# M868Hvrs1.net
KiCad netlist of a schematic drawn in EAGLE
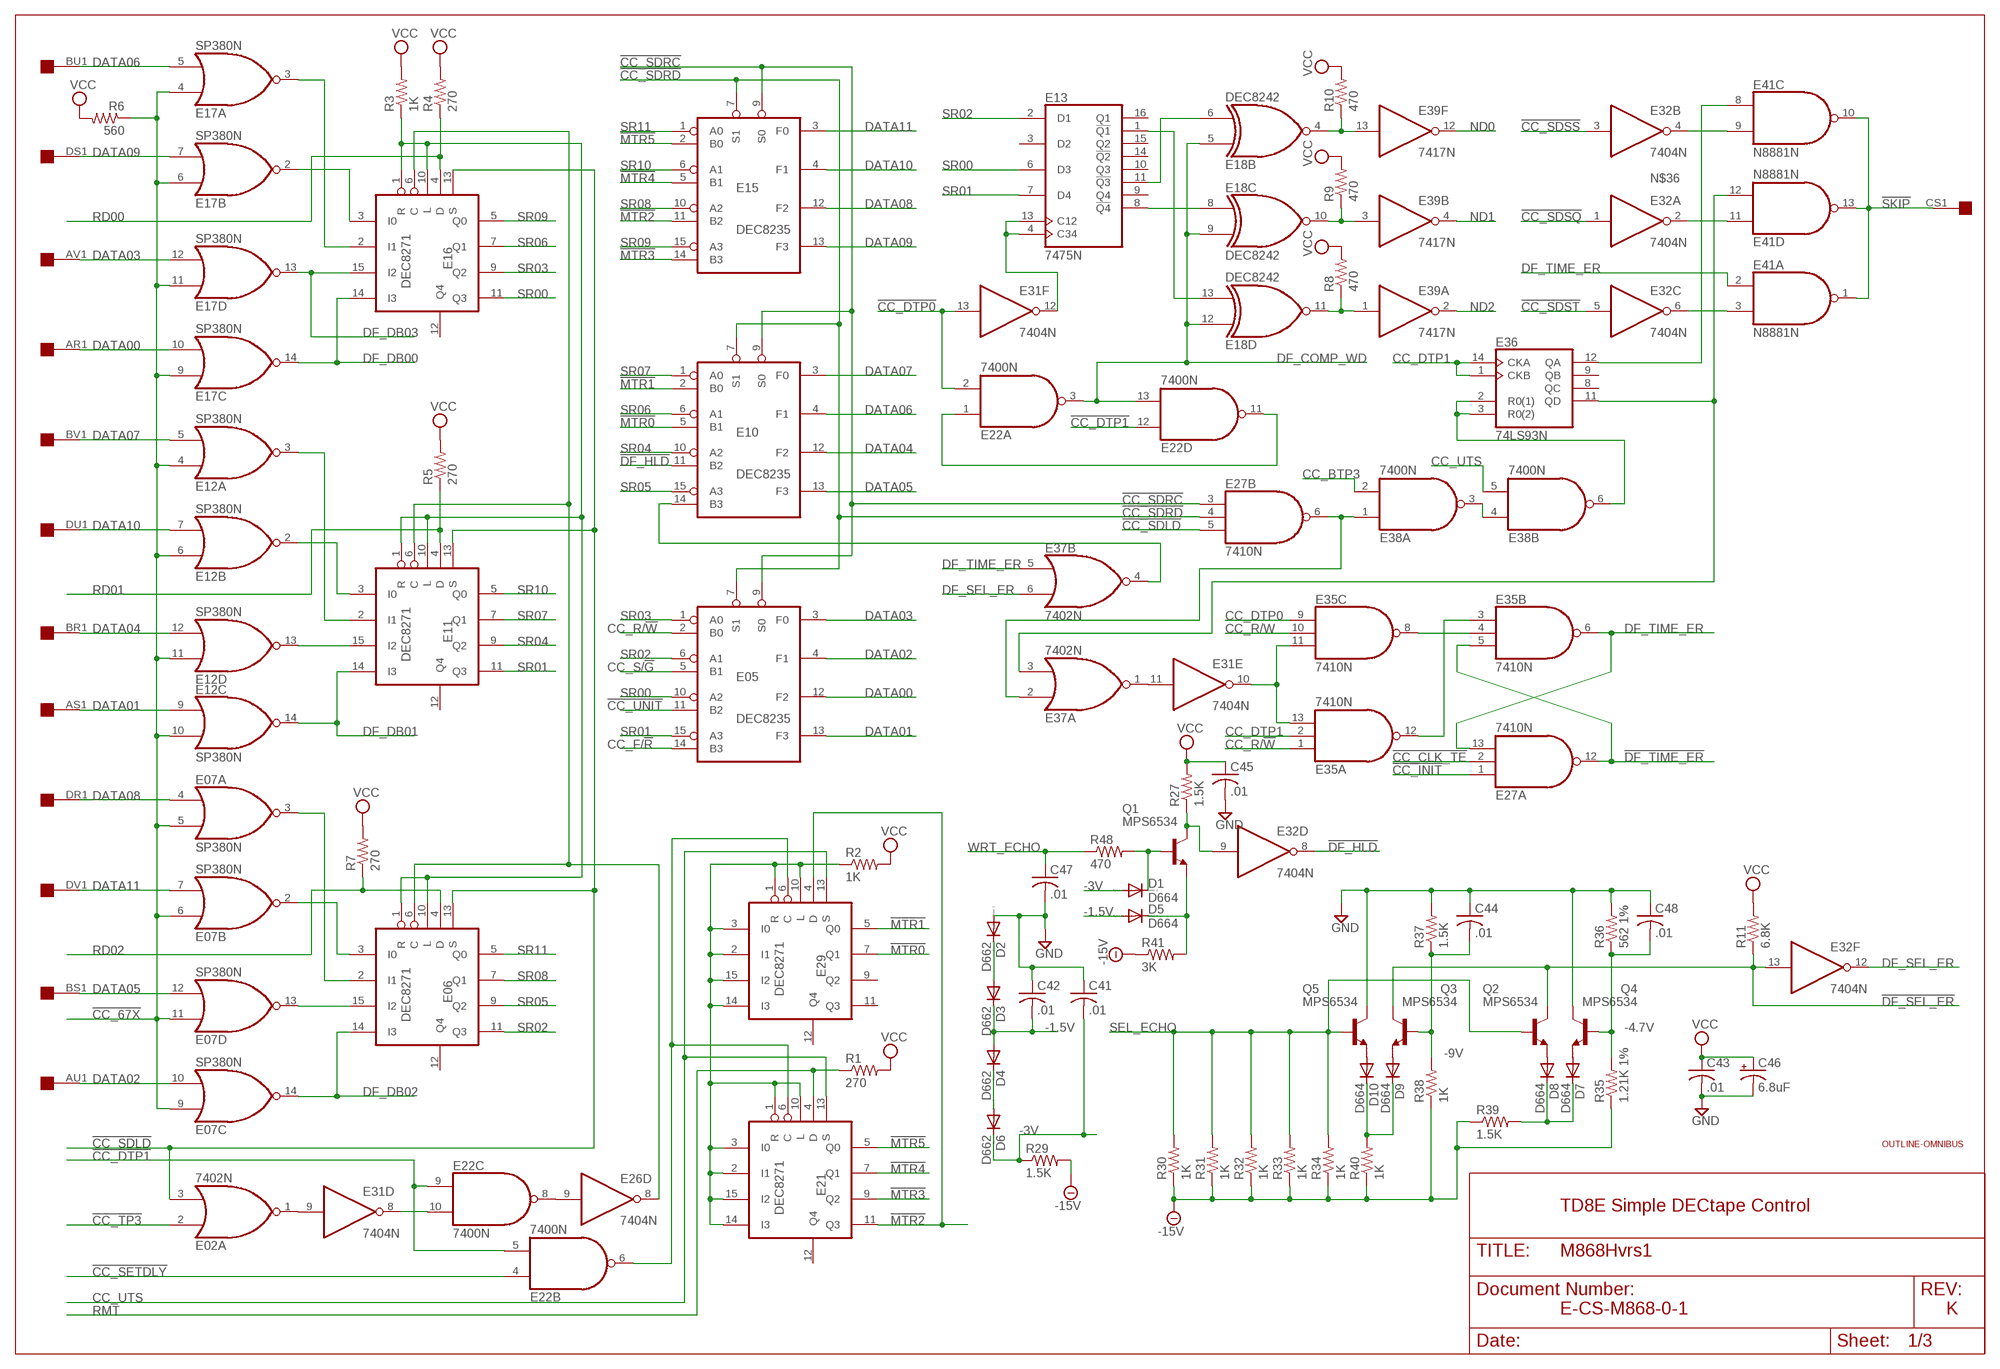
[diagram p0: schematic, sheet 1]
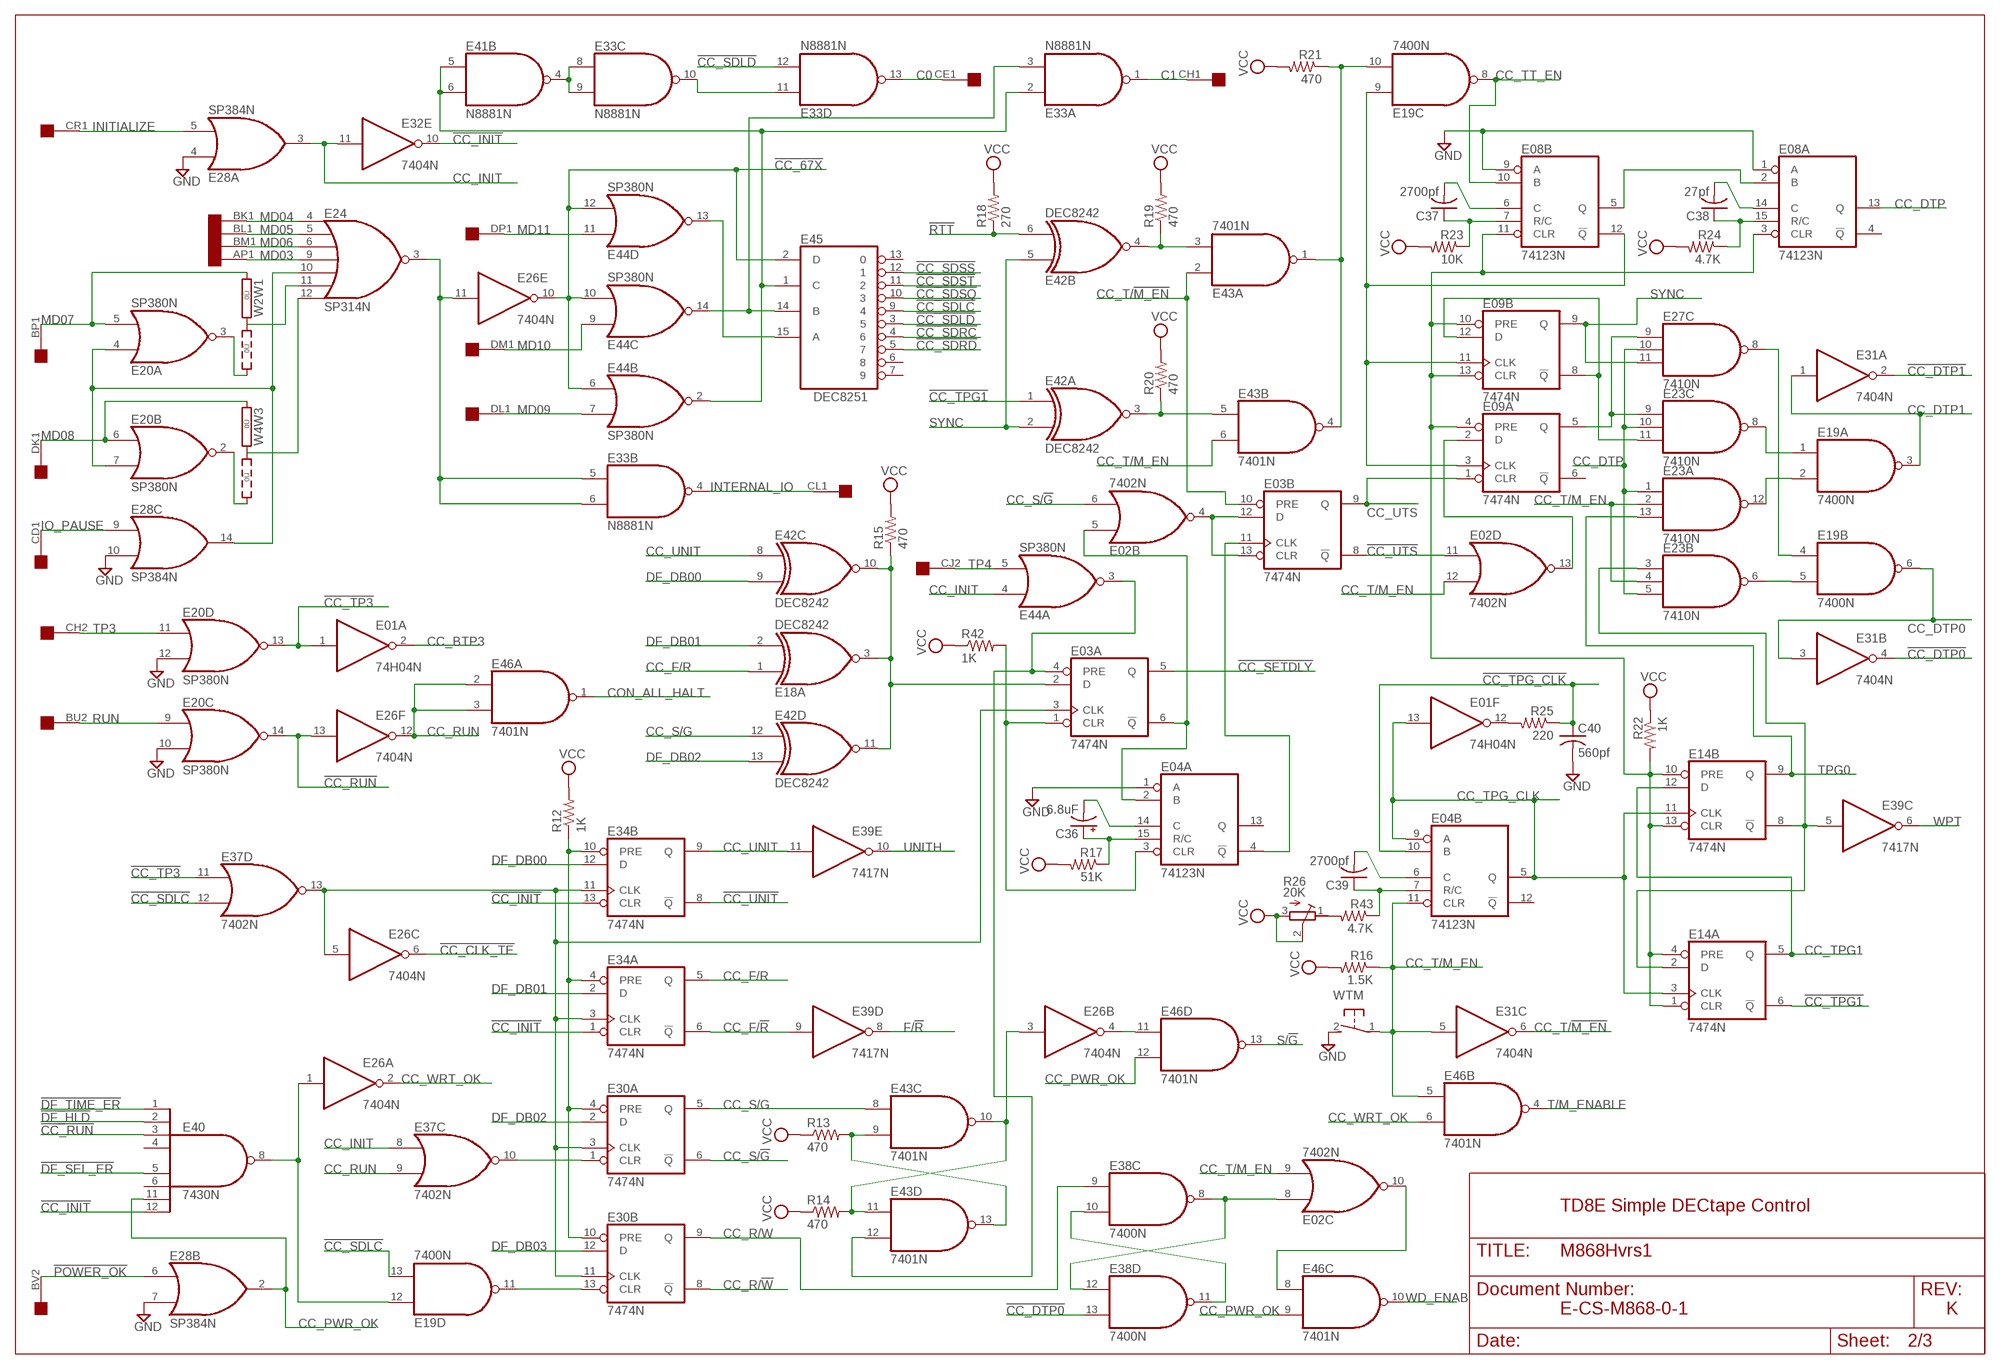
[diagram p1: schematic, sheet 2]
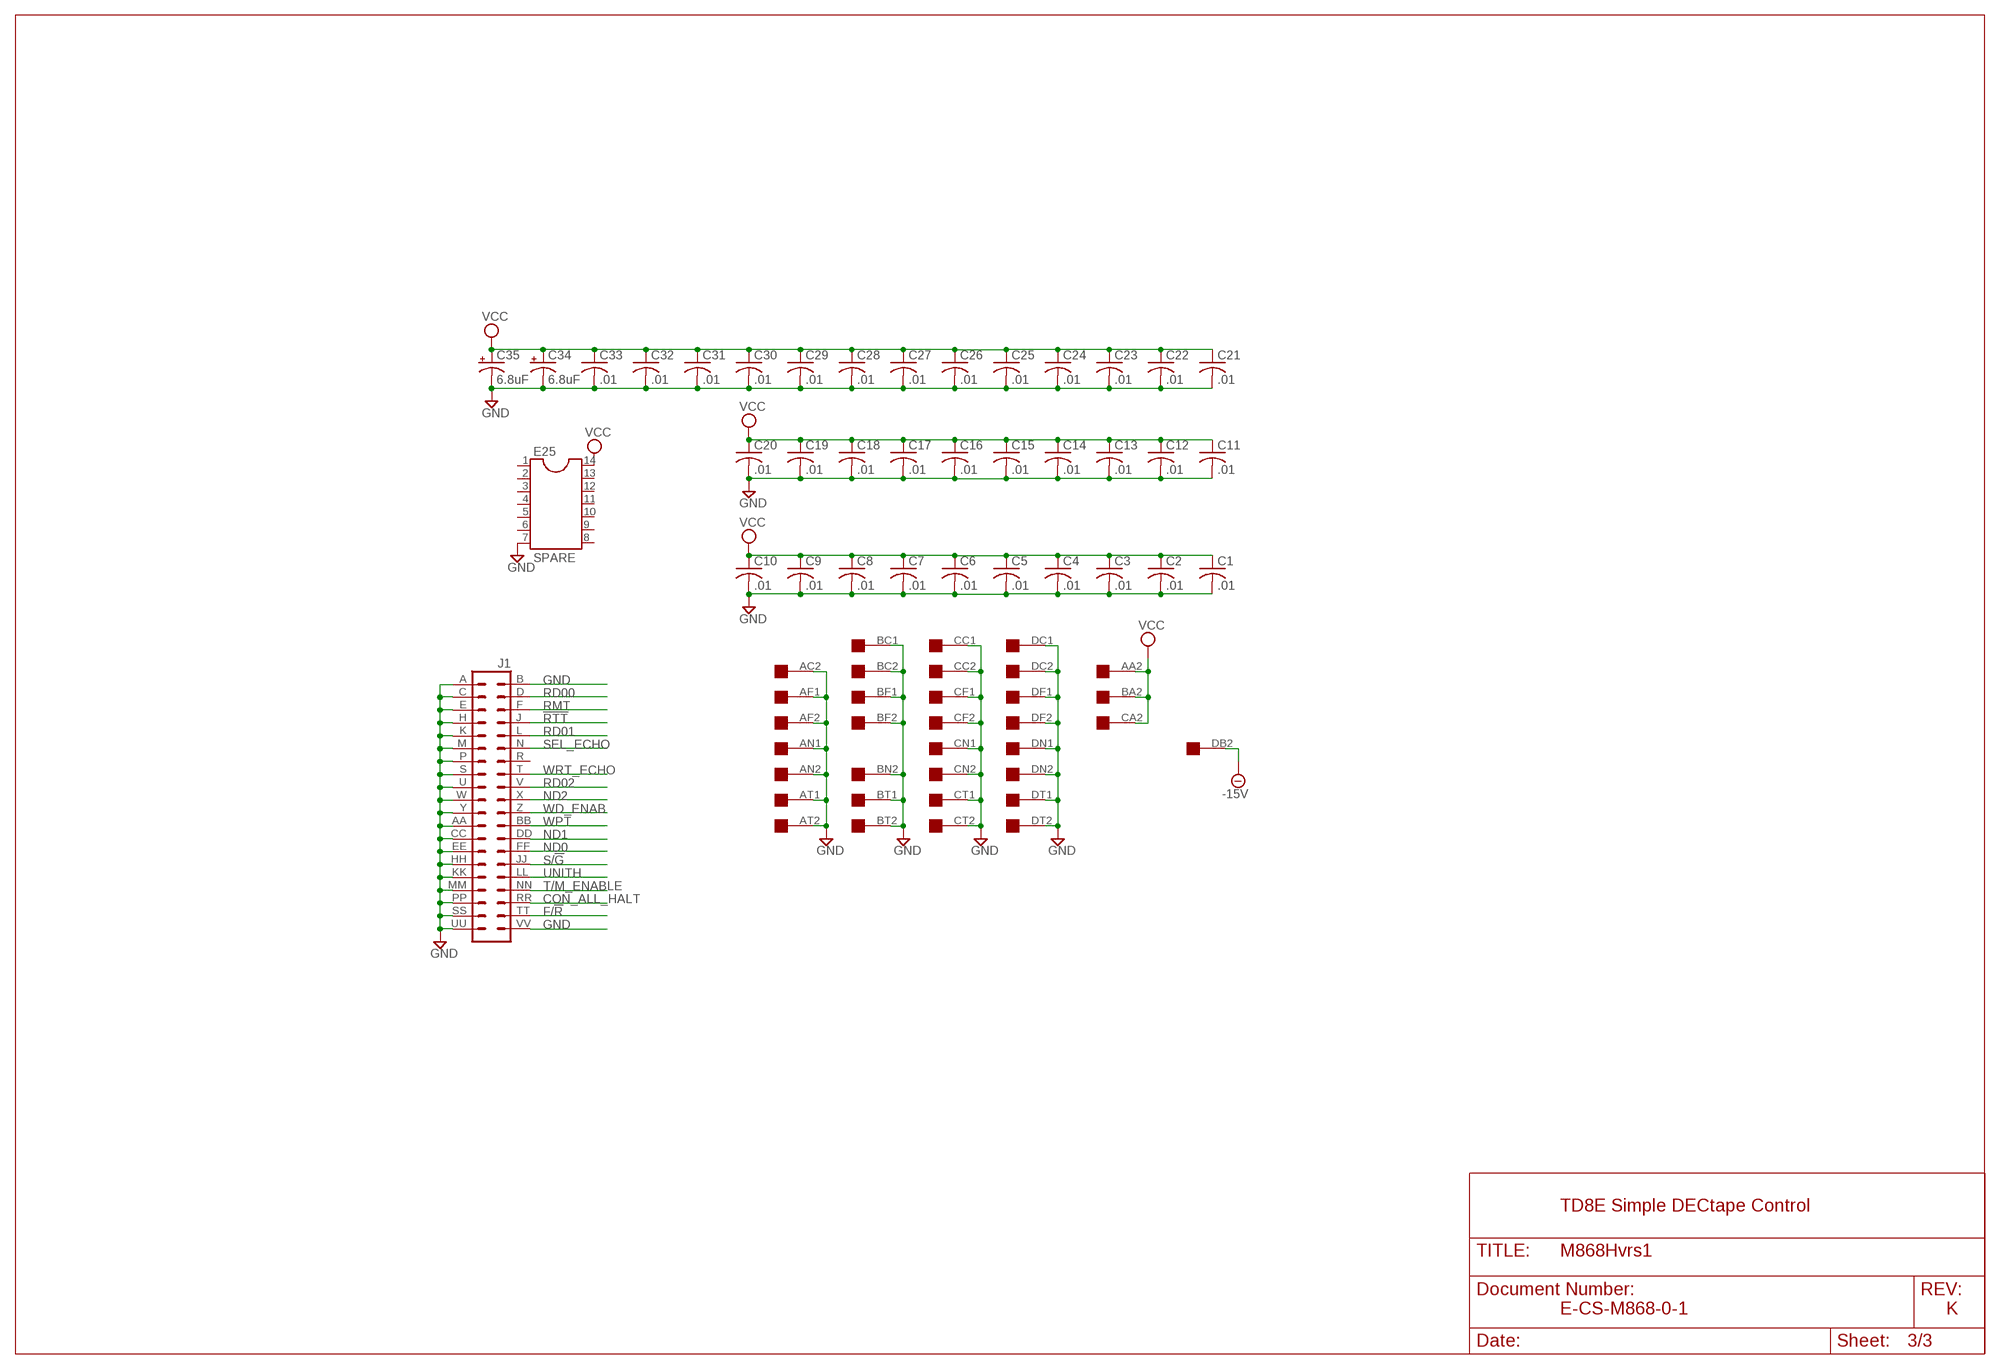
[diagram p2: schematic, sheet 3]

(export (version "E")
  (design (tool "Eeschema 10.0.6"))
  (components
    (comp (ref "C41")
      (value ".01")
      (footprint "eagle-import:C050-025X075")
      (libsource (lib "eagle-import") (part "C-US050-025X075"))
    )
    (comp (ref "C42")
      (value ".01")
      (footprint "eagle-import:C050-025X075")
      (libsource (lib "eagle-import") (part "C-US050-025X075"))
    )
    (comp (ref "C43")
      (value ".01")
      (footprint "eagle-import:C050-025X075")
      (libsource (lib "eagle-import") (part "C-US050-025X075"))
    )
    (comp (ref "C44")
      (value ".01")
      (footprint "eagle-import:C050-025X075")
      (libsource (lib "eagle-import") (part "C-US050-025X075"))
    )
    (comp (ref "C45")
      (value ".01")
      (footprint "eagle-import:C050-025X075")
      (libsource (lib "eagle-import") (part "C-US050-025X075"))
    )
    (comp (ref "C46")
      (value "6.8uF")
      (footprint "eagle-import:E12-8")
      (libsource (lib "eagle-import") (part "CPOL-USE20-8AXIAL"))
    )
    (comp (ref "C47")
      (value ".01")
      (footprint "eagle-import:C050-025X075")
      (libsource (lib "eagle-import") (part "C-US050-025X075"))
    )
    (comp (ref "C48")
      (value ".01")
      (footprint "eagle-import:C050-025X075")
      (libsource (lib "eagle-import") (part "C-US050-025X075"))
    )
    (comp (ref "D1")
      (value "D664")
      (footprint "eagle-import:DO35-10")
      (libsource (lib "eagle-import") (part "1N4148DO35-10"))
    )
    (comp (ref "D2")
      (value "D662")
      (footprint "eagle-import:DO35-10")
      (libsource (lib "eagle-import") (part "1N4148DO35-10"))
    )
    (comp (ref "D3")
      (value "D662")
      (footprint "eagle-import:DO35-10")
      (libsource (lib "eagle-import") (part "1N4148DO35-10"))
    )
    (comp (ref "D4")
      (value "D662")
      (footprint "eagle-import:DO35-10")
      (libsource (lib "eagle-import") (part "1N4148DO35-10"))
    )
    (comp (ref "D5")
      (value "D664")
      (footprint "eagle-import:DO35-10")
      (libsource (lib "eagle-import") (part "1N4148DO35-10"))
    )
    (comp (ref "D6")
      (value "D662")
      (footprint "eagle-import:DO35-10")
      (libsource (lib "eagle-import") (part "1N4148DO35-10"))
    )
    (comp (ref "D7")
      (value "D664")
      (footprint "eagle-import:DO35-10")
      (libsource (lib "eagle-import") (part "1N4148DO35-10"))
    )
    (comp (ref "D8")
      (value "D664")
      (footprint "eagle-import:DO35-10")
      (libsource (lib "eagle-import") (part "1N4148DO35-10"))
    )
    (comp (ref "D9")
      (value "D664")
      (footprint "eagle-import:DO35-10")
      (libsource (lib "eagle-import") (part "1N4148DO35-10"))
    )
    (comp (ref "D10")
      (value "D664")
      (footprint "eagle-import:DO35-10")
      (libsource (lib "eagle-import") (part "1N4148DO35-10"))
    )
    (comp (ref "E02")
      (value "7402N")
      (footprint "eagle-import:DIL14")
      (libsource (lib "eagle-import") (part "7402N"))
    )
    (comp (ref "E05")
      (value "DEC8235")
      (footprint "eagle-import:DIL16")
      (libsource (lib "eagle-import") (part "DEC8235"))
    )
    (comp (ref "E06")
      (value "DEC8271")
      (footprint "eagle-import:DIL16")
      (libsource (lib "eagle-import") (part "DEC8271"))
    )
    (comp (ref "E07")
      (value "SP380N")
      (footprint "eagle-import:DIL14")
      (libsource (lib "eagle-import") (part "SP380N"))
    )
    (comp (ref "E10")
      (value "DEC8235")
      (footprint "eagle-import:DIL16")
      (libsource (lib "eagle-import") (part "DEC8235"))
    )
    (comp (ref "E11")
      (value "DEC8271")
      (footprint "eagle-import:DIL16")
      (libsource (lib "eagle-import") (part "DEC8271"))
    )
    (comp (ref "E12")
      (value "SP380N")
      (footprint "eagle-import:DIL14")
      (libsource (lib "eagle-import") (part "SP380N"))
    )
    (comp (ref "E13")
      (value "7475N")
      (footprint "eagle-import:DIL16")
      (libsource (lib "eagle-import") (part "7475N"))
    )
    (comp (ref "E15")
      (value "DEC8235")
      (footprint "eagle-import:DIL16")
      (libsource (lib "eagle-import") (part "DEC8235"))
    )
    (comp (ref "E16")
      (value "DEC8271")
      (footprint "eagle-import:DIL16")
      (libsource (lib "eagle-import") (part "DEC8271"))
    )
    (comp (ref "E17")
      (value "SP380N")
      (footprint "eagle-import:DIL14")
      (libsource (lib "eagle-import") (part "SP380N"))
    )
    (comp (ref "E18")
      (value "DEC8242")
      (footprint "eagle-import:DIL14")
      (libsource (lib "eagle-import") (part "74266NLS"))
    )
    (comp (ref "E21")
      (value "DEC8271")
      (footprint "eagle-import:DIL16")
      (libsource (lib "eagle-import") (part "DEC8271"))
    )
    (comp (ref "E22")
      (value "7400N")
      (footprint "eagle-import:DIL14")
      (libsource (lib "eagle-import") (part "7400N"))
    )
    (comp (ref "E26")
      (value "7404N")
      (footprint "eagle-import:DIL14")
      (libsource (lib "eagle-import") (part "7404N"))
    )
    (comp (ref "E27")
      (value "7410N")
      (footprint "eagle-import:DIL14")
      (libsource (lib "eagle-import") (part "7410N"))
    )
    (comp (ref "E29")
      (value "DEC8271")
      (footprint "eagle-import:DIL16")
      (libsource (lib "eagle-import") (part "DEC8271"))
    )
    (comp (ref "E31")
      (value "7404N")
      (footprint "eagle-import:DIL14")
      (libsource (lib "eagle-import") (part "7404N"))
    )
    (comp (ref "E32")
      (value "7404N")
      (footprint "eagle-import:DIL14")
      (libsource (lib "eagle-import") (part "7404N"))
    )
    (comp (ref "E35")
      (value "7410N")
      (footprint "eagle-import:DIL14")
      (libsource (lib "eagle-import") (part "7410N"))
    )
    (comp (ref "E36")
      (value "74LS93N")
      (footprint "eagle-import:DIL14")
      (libsource (lib "eagle-import") (part "7493NLS"))
    )
    (comp (ref "E37")
      (value "7402N")
      (footprint "eagle-import:DIL14")
      (libsource (lib "eagle-import") (part "7402N"))
    )
    (comp (ref "E38")
      (value "7400N")
      (footprint "eagle-import:DIL14")
      (libsource (lib "eagle-import") (part "7400N"))
    )
    (comp (ref "E39")
      (value "7417N")
      (footprint "eagle-import:DIL14")
      (libsource (lib "eagle-import") (part "7417N"))
    )
    (comp (ref "E41")
      (value "N8881N")
      (footprint "eagle-import:DIL14")
      (libsource (lib "eagle-import") (part "N8881N"))
    )
    (comp (ref "EDGE$")
      (value "QUAD")
      (footprint "eagle-import:EDGE-CON8")
      (libsource (lib "eagle-import") (part "QUAD"))
    )
    (comp (ref "Q1")
      (value "MPS6534")
      (footprint "eagle-import:TO5")
      (libsource (lib "eagle-import") (part "2N2219"))
    )
    (comp (ref "Q2")
      (value "MPS6534")
      (footprint "eagle-import:TO5")
      (libsource (lib "eagle-import") (part "2N2219"))
    )
    (comp (ref "Q3")
      (value "MPS6534")
      (footprint "eagle-import:TO5")
      (libsource (lib "eagle-import") (part "2N2219"))
    )
    (comp (ref "Q4")
      (value "MPS6534")
      (footprint "eagle-import:TO5")
      (libsource (lib "eagle-import") (part "2N2219"))
    )
    (comp (ref "Q5")
      (value "MPS6534")
      (footprint "eagle-import:TO5")
      (libsource (lib "eagle-import") (part "2N2219"))
    )
    (comp (ref "R1")
      (value "270")
      (footprint "eagle-import:0207_10")
      (libsource (lib "eagle-import") (part "R-US_0207/10"))
    )
    (comp (ref "R2")
      (value "1K")
      (footprint "eagle-import:0207_10")
      (libsource (lib "eagle-import") (part "R-US_0207/10"))
    )
    (comp (ref "R3")
      (value "1K")
      (footprint "eagle-import:0207_10")
      (libsource (lib "eagle-import") (part "R-US_0207/10"))
    )
    (comp (ref "R4")
      (value "270")
      (footprint "eagle-import:0207_10")
      (libsource (lib "eagle-import") (part "R-US_0207/10"))
    )
    (comp (ref "R5")
      (value "270")
      (footprint "eagle-import:0207_10")
      (libsource (lib "eagle-import") (part "R-US_0207/10"))
    )
    (comp (ref "R6")
      (value "560")
      (footprint "eagle-import:0207_10")
      (libsource (lib "eagle-import") (part "R-US_0207/10"))
    )
    (comp (ref "R7")
      (value "270")
      (footprint "eagle-import:0207_10")
      (libsource (lib "eagle-import") (part "R-US_0207/10"))
    )
    (comp (ref "R8")
      (value "470")
      (footprint "eagle-import:0207_10")
      (libsource (lib "eagle-import") (part "R-US_0207/10"))
    )
    (comp (ref "R9")
      (value "470")
      (footprint "eagle-import:0207_10")
      (libsource (lib "eagle-import") (part "R-US_0207/10"))
    )
    (comp (ref "R10")
      (value "470")
      (footprint "eagle-import:0207_10")
      (libsource (lib "eagle-import") (part "R-US_0207/10"))
    )
    (comp (ref "R11")
      (value "6.8K")
      (footprint "eagle-import:0207_10")
      (libsource (lib "eagle-import") (part "R-US_0207/10"))
    )
    (comp (ref "R27")
      (value "1.5K")
      (footprint "eagle-import:0207_10")
      (libsource (lib "eagle-import") (part "R-US_0207/10"))
    )
    (comp (ref "R29")
      (value "1.5K")
      (footprint "eagle-import:0207_10")
      (libsource (lib "eagle-import") (part "R-US_0207/10"))
    )
    (comp (ref "R30")
      (value "1K")
      (footprint "eagle-import:0207_10")
      (libsource (lib "eagle-import") (part "R-US_0207/10"))
    )
    (comp (ref "R31")
      (value "1K")
      (footprint "eagle-import:0207_10")
      (libsource (lib "eagle-import") (part "R-US_0207/10"))
    )
    (comp (ref "R32")
      (value "1K")
      (footprint "eagle-import:0207_10")
      (libsource (lib "eagle-import") (part "R-US_0207/10"))
    )
    (comp (ref "R33")
      (value "1K")
      (footprint "eagle-import:0207_10")
      (libsource (lib "eagle-import") (part "R-US_0207/10"))
    )
    (comp (ref "R34")
      (value "1K")
      (footprint "eagle-import:0207_10")
      (libsource (lib "eagle-import") (part "R-US_0207/10"))
    )
    (comp (ref "R35")
      (value "1.21K 1%")
      (footprint "eagle-import:0207_15")
      (libsource (lib "eagle-import") (part "R-US_0207/15"))
    )
    (comp (ref "R36")
      (value "562 1%")
      (footprint "eagle-import:0207_15")
      (libsource (lib "eagle-import") (part "R-US_0207/15"))
    )
    (comp (ref "R37")
      (value "1.5K")
      (footprint "eagle-import:0207_10")
      (libsource (lib "eagle-import") (part "R-US_0207/10"))
    )
    (comp (ref "R38")
      (value "1K")
      (footprint "eagle-import:0207_10")
      (libsource (lib "eagle-import") (part "R-US_0207/10"))
    )
    (comp (ref "R39")
      (value "1.5K")
      (footprint "eagle-import:0207_10")
      (libsource (lib "eagle-import") (part "R-US_0207/10"))
    )
    (comp (ref "R40")
      (value "1K")
      (footprint "eagle-import:0207_10")
      (libsource (lib "eagle-import") (part "R-US_0207/10"))
    )
    (comp (ref "R41")
      (value "3K")
      (footprint "eagle-import:0207_10")
      (libsource (lib "eagle-import") (part "R-US_0207/10"))
    )
    (comp (ref "R48")
      (value "470")
      (footprint "eagle-import:0207_10")
      (libsource (lib "eagle-import") (part "R-US_0207/10"))
    )
    (comp (ref "U$1")
      (value "OUTLINE-OMNIBUS")
      (footprint "eagle-import:OMNIBUS")
      (libsource (lib "eagle-import") (part "OUTLINE-OMNIBUS"))
    )
    (comp (ref "C1")
      (value ".01")
      (footprint "eagle-import:C050-025X075")
      (libsource (lib "eagle-import") (part "C-US050-025X075"))
    )
    (comp (ref "C2")
      (value ".01")
      (footprint "eagle-import:C050-025X075")
      (libsource (lib "eagle-import") (part "C-US050-025X075"))
    )
    (comp (ref "C3")
      (value ".01")
      (footprint "eagle-import:C050-025X075")
      (libsource (lib "eagle-import") (part "C-US050-025X075"))
    )
    (comp (ref "C4")
      (value ".01")
      (footprint "eagle-import:C050-025X075")
      (libsource (lib "eagle-import") (part "C-US050-025X075"))
    )
    (comp (ref "C5")
      (value ".01")
      (footprint "eagle-import:C050-025X075")
      (libsource (lib "eagle-import") (part "C-US050-025X075"))
    )
    (comp (ref "C6")
      (value ".01")
      (footprint "eagle-import:C050-025X075")
      (libsource (lib "eagle-import") (part "C-US050-025X075"))
    )
    (comp (ref "C7")
      (value ".01")
      (footprint "eagle-import:C050-025X075")
      (libsource (lib "eagle-import") (part "C-US050-025X075"))
    )
    (comp (ref "C8")
      (value ".01")
      (footprint "eagle-import:C050-025X075")
      (libsource (lib "eagle-import") (part "C-US050-025X075"))
    )
    (comp (ref "C9")
      (value ".01")
      (footprint "eagle-import:C050-025X075")
      (libsource (lib "eagle-import") (part "C-US050-025X075"))
    )
    (comp (ref "C10")
      (value ".01")
      (footprint "eagle-import:C050-025X075")
      (libsource (lib "eagle-import") (part "C-US050-025X075"))
    )
    (comp (ref "C11")
      (value ".01")
      (footprint "eagle-import:C050-025X075")
      (libsource (lib "eagle-import") (part "C-US050-025X075"))
    )
    (comp (ref "C12")
      (value ".01")
      (footprint "eagle-import:C050-025X075")
      (libsource (lib "eagle-import") (part "C-US050-025X075"))
    )
    (comp (ref "C13")
      (value ".01")
      (footprint "eagle-import:C050-025X075")
      (libsource (lib "eagle-import") (part "C-US050-025X075"))
    )
    (comp (ref "C14")
      (value ".01")
      (footprint "eagle-import:C050-025X075")
      (libsource (lib "eagle-import") (part "C-US050-025X075"))
    )
    (comp (ref "C15")
      (value ".01")
      (footprint "eagle-import:C050-025X075")
      (libsource (lib "eagle-import") (part "C-US050-025X075"))
    )
    (comp (ref "C16")
      (value ".01")
      (footprint "eagle-import:C050-025X075")
      (libsource (lib "eagle-import") (part "C-US050-025X075"))
    )
    (comp (ref "C17")
      (value ".01")
      (footprint "eagle-import:C050-025X075")
      (libsource (lib "eagle-import") (part "C-US050-025X075"))
    )
    (comp (ref "C18")
      (value ".01")
      (footprint "eagle-import:C050-025X075")
      (libsource (lib "eagle-import") (part "C-US050-025X075"))
    )
    (comp (ref "C19")
      (value ".01")
      (footprint "eagle-import:C050-025X075")
      (libsource (lib "eagle-import") (part "C-US050-025X075"))
    )
    (comp (ref "C20")
      (value ".01")
      (footprint "eagle-import:C050-025X075")
      (libsource (lib "eagle-import") (part "C-US050-025X075"))
    )
    (comp (ref "C21")
      (value ".01")
      (footprint "eagle-import:C050-025X075")
      (libsource (lib "eagle-import") (part "C-US050-025X075"))
    )
    (comp (ref "C22")
      (value ".01")
      (footprint "eagle-import:C050-025X075")
      (libsource (lib "eagle-import") (part "C-US050-025X075"))
    )
    (comp (ref "C23")
      (value ".01")
      (footprint "eagle-import:C050-025X075")
      (libsource (lib "eagle-import") (part "C-US050-025X075"))
    )
    (comp (ref "C24")
      (value ".01")
      (footprint "eagle-import:C050-025X075")
      (libsource (lib "eagle-import") (part "C-US050-025X075"))
    )
    (comp (ref "C25")
      (value ".01")
      (footprint "eagle-import:C050-025X075")
      (libsource (lib "eagle-import") (part "C-US050-025X075"))
    )
    (comp (ref "C26")
      (value ".01")
      (footprint "eagle-import:C050-025X075")
      (libsource (lib "eagle-import") (part "C-US050-025X075"))
    )
    (comp (ref "C27")
      (value ".01")
      (footprint "eagle-import:C050-025X075")
      (libsource (lib "eagle-import") (part "C-US050-025X075"))
    )
    (comp (ref "C28")
      (value ".01")
      (footprint "eagle-import:C050-025X075")
      (libsource (lib "eagle-import") (part "C-US050-025X075"))
    )
    (comp (ref "C29")
      (value ".01")
      (footprint "eagle-import:C050-025X075")
      (libsource (lib "eagle-import") (part "C-US050-025X075"))
    )
    (comp (ref "C30")
      (value ".01")
      (footprint "eagle-import:C050-025X075")
      (libsource (lib "eagle-import") (part "C-US050-025X075"))
    )
    (comp (ref "C31")
      (value ".01")
      (footprint "eagle-import:C050-025X075")
      (libsource (lib "eagle-import") (part "C-US050-025X075"))
    )
    (comp (ref "C32")
      (value ".01")
      (footprint "eagle-import:C050-025X075")
      (libsource (lib "eagle-import") (part "C-US050-025X075"))
    )
    (comp (ref "C33")
      (value ".01")
      (footprint "eagle-import:C050-025X075")
      (libsource (lib "eagle-import") (part "C-US050-025X075"))
    )
    (comp (ref "C34")
      (value "6.8uF")
      (footprint "eagle-import:E12-8")
      (libsource (lib "eagle-import") (part "CPOL-USE20-8AXIAL"))
    )
    (comp (ref "C35")
      (value "6.8uF")
      (footprint "eagle-import:E12-8")
      (libsource (lib "eagle-import") (part "CPOL-USE20-8AXIAL"))
    )
    (comp (ref "E25")
      (value "SPARE")
      (footprint "eagle-import:DIL14")
      (libsource (lib "eagle-import") (part "DIL14"))
    )
    (comp (ref "J1")
      (value "DEC40PINH")
      (footprint "eagle-import:DEC40PINH")
      (libsource (lib "eagle-import") (part "DEC40PINH"))
    )
    (comp (ref "C36")
      (value "6.8uF")
      (footprint "eagle-import:E12-8")
      (libsource (lib "eagle-import") (part "CPOL-USE20-8AXIAL"))
    )
    (comp (ref "C37")
      (value "2700pf")
      (footprint "eagle-import:C102-043X133")
      (libsource (lib "eagle-import") (part "C-US102-043X133"))
    )
    (comp (ref "C38")
      (value "27pf")
      (footprint "eagle-import:C050-025X075")
      (libsource (lib "eagle-import") (part "C-US050-025X075"))
    )
    (comp (ref "C39")
      (value "2700pf")
      (footprint "eagle-import:C102-043X133")
      (libsource (lib "eagle-import") (part "C-US102-043X133"))
    )
    (comp (ref "C40")
      (value "560pf")
      (footprint "eagle-import:C075-032X103")
      (libsource (lib "eagle-import") (part "C-US075-032X103"))
    )
    (comp (ref "E01")
      (value "74H04N")
      (footprint "eagle-import:DIL14")
      (libsource (lib "eagle-import") (part "7404NS"))
    )
    (comp (ref "E03")
      (value "7474N")
      (footprint "eagle-import:DIL14")
      (libsource (lib "eagle-import") (part "7474NS"))
    )
    (comp (ref "E04")
      (value "74123N")
      (footprint "eagle-import:DIL16")
      (libsource (lib "eagle-import") (part "74123N"))
    )
    (comp (ref "E08")
      (value "74123N")
      (footprint "eagle-import:DIL16")
      (libsource (lib "eagle-import") (part "74123N"))
    )
    (comp (ref "E09")
      (value "7474N")
      (footprint "eagle-import:DIL14")
      (libsource (lib "eagle-import") (part "7474NS"))
    )
    (comp (ref "E14")
      (value "7474N")
      (footprint "eagle-import:DIL14")
      (libsource (lib "eagle-import") (part "7474NS"))
    )
    (comp (ref "E19")
      (value "7400N")
      (footprint "eagle-import:DIL14")
      (libsource (lib "eagle-import") (part "7400N"))
    )
    (comp (ref "E20")
      (value "SP380N")
      (footprint "eagle-import:DIL14")
      (libsource (lib "eagle-import") (part "SP380N"))
    )
    (comp (ref "E23")
      (value "7410N")
      (footprint "eagle-import:DIL14")
      (libsource (lib "eagle-import") (part "7410N"))
    )
    (comp (ref "E24")
      (value "SP314N")
      (footprint "eagle-import:DIL14")
      (libsource (lib "eagle-import") (part "SP314N"))
    )
    (comp (ref "E28")
      (value "SP384N")
      (footprint "eagle-import:DIL14")
      (libsource (lib "eagle-import") (part "SP384N"))
    )
    (comp (ref "E30")
      (value "7474N")
      (footprint "eagle-import:DIL14")
      (libsource (lib "eagle-import") (part "7474NS"))
    )
    (comp (ref "E33")
      (value "N8881N")
      (footprint "eagle-import:DIL14")
      (libsource (lib "eagle-import") (part "N8881N"))
    )
    (comp (ref "E34")
      (value "7474N")
      (footprint "eagle-import:DIL14")
      (libsource (lib "eagle-import") (part "7474NS"))
    )
    (comp (ref "E40")
      (value "7430N")
      (footprint "eagle-import:DIL14")
      (libsource (lib "eagle-import") (part "7430N"))
    )
    (comp (ref "E42")
      (value "DEC8242")
      (footprint "eagle-import:DIL14")
      (libsource (lib "eagle-import") (part "74266NLS"))
    )
    (comp (ref "E43")
      (value "7401N")
      (footprint "eagle-import:DIL14")
      (libsource (lib "eagle-import") (part "7401NLS"))
    )
    (comp (ref "E44")
      (value "SP380N")
      (footprint "eagle-import:DIL14")
      (libsource (lib "eagle-import") (part "SP380N"))
    )
    (comp (ref "E45")
      (value "DEC8251")
      (footprint "eagle-import:DIL16")
      (libsource (lib "eagle-import") (part "DEC8251"))
    )
    (comp (ref "E46")
      (value "7401N")
      (footprint "eagle-import:DIL14")
      (libsource (lib "eagle-import") (part "7401NLS"))
    )
    (comp (ref "R12")
      (value "1K")
      (footprint "eagle-import:0207_10")
      (libsource (lib "eagle-import") (part "R-US_0207/10"))
    )
    (comp (ref "R13")
      (value "470")
      (footprint "eagle-import:0207_10")
      (libsource (lib "eagle-import") (part "R-US_0207/10"))
    )
    (comp (ref "R14")
      (value "470")
      (footprint "eagle-import:0207_10")
      (libsource (lib "eagle-import") (part "R-US_0207/10"))
    )
    (comp (ref "R15")
      (value "470")
      (footprint "eagle-import:0207_10")
      (libsource (lib "eagle-import") (part "R-US_0207/10"))
    )
    (comp (ref "R16")
      (value "1.5K")
      (footprint "eagle-import:0207_10")
      (libsource (lib "eagle-import") (part "R-US_0207/10"))
    )
    (comp (ref "R17")
      (value "51K")
      (footprint "eagle-import:0207_10")
      (libsource (lib "eagle-import") (part "R-US_0207/10"))
    )
    (comp (ref "R18")
      (value "270")
      (footprint "eagle-import:0207_10")
      (libsource (lib "eagle-import") (part "R-US_0207/10"))
    )
    (comp (ref "R19")
      (value "470")
      (footprint "eagle-import:0207_10")
      (libsource (lib "eagle-import") (part "R-US_0207/10"))
    )
    (comp (ref "R20")
      (value "470")
      (footprint "eagle-import:0207_10")
      (libsource (lib "eagle-import") (part "R-US_0207/10"))
    )
    (comp (ref "R21")
      (value "470")
      (footprint "eagle-import:0207_10")
      (libsource (lib "eagle-import") (part "R-US_0207/10"))
    )
    (comp (ref "R22")
      (value "1K")
      (footprint "eagle-import:0207_10")
      (libsource (lib "eagle-import") (part "R-US_0207/10"))
    )
    (comp (ref "R23")
      (value "10K")
      (footprint "eagle-import:0207_10")
      (libsource (lib "eagle-import") (part "R-US_0207/10"))
    )
    (comp (ref "R24")
      (value "4.7K")
      (footprint "eagle-import:0207_10")
      (libsource (lib "eagle-import") (part "R-US_0207/10"))
    )
    (comp (ref "R25")
      (value "220")
      (footprint "eagle-import:0207_10")
      (libsource (lib "eagle-import") (part "R-US_0207/10"))
    )
    (comp (ref "R26")
      (value "20K")
      (footprint "eagle-import:3006Y")
      (libsource (lib "eagle-import") (part "275P"))
    )
    (comp (ref "R42")
      (value "1K")
      (footprint "eagle-import:0207_10")
      (libsource (lib "eagle-import") (part "R-US_0207/10"))
    )
    (comp (ref "R43")
      (value "4.7K")
      (footprint "eagle-import:0207_10")
      (libsource (lib "eagle-import") (part "R-US_0207/10"))
    )
    (comp (ref "W2W1")
      (value "0R2")
      (footprint "eagle-import:0R2_10")
      (libsource (lib "eagle-import") (part "0R2"))
    )
    (comp (ref "W4W3")
      (value "0R2")
      (footprint "eagle-import:0R2_10")
      (libsource (lib "eagle-import") (part "0R2"))
    )
    (comp (ref "WTM")
      (value "31-XX")
      (footprint "eagle-import:B3F-31XX")
      (fields (field (name "MPN") "B3F-3100"))
      (libsource (lib "eagle-import") (part "31-XX"))
    )
  )
  (nets
    (net (code "1") (name "-1.5V") (class "Default")
      (node (ref "C42") (pin "2") (pinfunction "2_2") (pintype "passive"))
      (node (ref "D3") (pin "C") (pinfunction "C_C") (pintype "passive"))
      (node (ref "D4") (pin "A") (pinfunction "A_A") (pintype "passive"))
      (node (ref "D5") (pin "A") (pinfunction "A_A") (pintype "passive"))
    )
    (net (code "2") (name "-3V") (class "Default")
      (node (ref "C41") (pin "2") (pinfunction "2_2") (pintype "passive"))
      (node (ref "D1") (pin "A") (pinfunction "A_A") (pintype "passive"))
      (node (ref "D6") (pin "C") (pinfunction "C_C") (pintype "passive"))
      (node (ref "R29") (pin "1") (pinfunction "1_1") (pintype "passive"))
    )
    (net (code "3") (name "-4.7V") (class "Default")
      (node (ref "C48") (pin "2") (pinfunction "2_2") (pintype "passive"))
      (node (ref "Q4") (pin "2") (pinfunction "B_2") (pintype "passive"))
      (node (ref "R35") (pin "2") (pinfunction "2_2") (pintype "passive"))
      (node (ref "R36") (pin "1") (pinfunction "1_1") (pintype "passive"))
    )
    (net (code "4") (name "-9V") (class "Default")
      (node (ref "C44") (pin "2") (pinfunction "2_2") (pintype "passive"))
      (node (ref "Q3") (pin "2") (pinfunction "B_2") (pintype "passive"))
      (node (ref "R37") (pin "1") (pinfunction "1_1") (pintype "passive"))
      (node (ref "R38") (pin "2") (pinfunction "2_2") (pintype "passive"))
    )
    (net (code "5") (name "-15V") (class "Default")
      (node (ref "EDGE$") (pin "DB2") (pinfunction "1_DB2") (pintype "bidirectional"))
      (node (ref "R29") (pin "2") (pinfunction "2_2") (pintype "passive"))
      (node (ref "R30") (pin "1") (pinfunction "1_1") (pintype "passive"))
      (node (ref "R31") (pin "1") (pinfunction "1_1") (pintype "passive"))
      (node (ref "R32") (pin "1") (pinfunction "1_1") (pintype "passive"))
      (node (ref "R33") (pin "1") (pinfunction "1_1") (pintype "passive"))
      (node (ref "R34") (pin "1") (pinfunction "1_1") (pintype "passive"))
      (node (ref "R35") (pin "1") (pinfunction "1_1") (pintype "passive"))
      (node (ref "R38") (pin "1") (pinfunction "1_1") (pintype "passive"))
      (node (ref "R39") (pin "1") (pinfunction "1_1") (pintype "passive"))
      (node (ref "R40") (pin "1") (pinfunction "1_1") (pintype "passive"))
      (node (ref "R41") (pin "1") (pinfunction "1_1") (pintype "passive"))
    )
    (net (code "6") (name "C0") (class "Default")
      (node (ref "E33") (pin "13") (pinfunction "O_13") (pintype "open_collector"))
      (node (ref "EDGE$") (pin "CE1") (pinfunction "1_CE1") (pintype "bidirectional"))
    )
    (net (code "7") (name "C1") (class "Default")
      (node (ref "E33") (pin "1") (pinfunction "O_1") (pintype "open_collector"))
      (node (ref "EDGE$") (pin "CH1") (pinfunction "1_CH1") (pintype "bidirectional"))
    )
    (net (code "8") (name "CC_BTP3") (class "Default")
      (node (ref "E01") (pin "2") (pinfunction "O_2") (pintype "output"))
      (node (ref "E38") (pin "2") (pinfunction "I1_2") (pintype "input"))
    )
    (net (code "9") (name "CC_DTP") (class "Default")
      (node (ref "E08") (pin "13") (pinfunction "Q_13") (pintype "output"))
      (node (ref "E23") (pin "1") (pinfunction "I0_1") (pintype "input"))
      (node (ref "E23") (pin "10") (pinfunction "I1_10") (pintype "input"))
      (node (ref "E23") (pin "5") (pinfunction "I2_5") (pintype "input"))
      (node (ref "E27") (pin "10") (pinfunction "I1_10") (pintype "input"))
    )
    (net (code "10") (name "CC_DTP0") (class "Default")
      (node (ref "E19") (pin "6") (pinfunction "O_6") (pintype "output"))
      (node (ref "E31") (pin "3") (pinfunction "I_3") (pintype "input"))
      (node (ref "E35") (pin "9") (pinfunction "I0_9") (pintype "input"))
    )
    (net (code "11") (name "CC_DTP1") (class "Default")
      (node (ref "E19") (pin "3") (pinfunction "O_3") (pintype "output"))
      (node (ref "E31") (pin "1") (pinfunction "I_1") (pintype "input"))
      (node (ref "E35") (pin "2") (pinfunction "I1_2") (pintype "input"))
      (node (ref "E36") (pin "1") (pinfunction "CKB_1") (pintype "input"))
      (node (ref "E36") (pin "14") (pinfunction "CKA_14") (pintype "input"))
    )
    (net (code "12") (name "CC_F{slash}R") (class "Default")
      (node (ref "E18") (pin "1") (pinfunction "I0_1") (pintype "input"))
      (node (ref "E34") (pin "5") (pinfunction "Q_5") (pintype "output"))
    )
    (net (code "13") (name "CC_F{slash}~{R}") (class "Default")
      (node (ref "E05") (pin "14") (pinfunction "B3_14") (pintype "input"))
      (node (ref "E34") (pin "6") (pinfunction "~{Q}_6") (pintype "output"))
      (node (ref "E39") (pin "9") (pinfunction "I_9") (pintype "input"))
    )
    (net (code "14") (name "CC_INIT") (class "Default")
      (node (ref "E28") (pin "3") (pinfunction "O_3") (pintype "output"))
      (node (ref "E32") (pin "11") (pinfunction "I_11") (pintype "input"))
      (node (ref "E37") (pin "8") (pinfunction "I0_8") (pintype "input"))
      (node (ref "E44") (pin "4") (pinfunction "I0_4") (pintype "input"))
    )
    (net (code "15") (name "CC_PWR_OK") (class "Default")
      (node (ref "E28") (pin "2") (pinfunction "O_2") (pintype "output"))
      (node (ref "E40") (pin "11") (pinfunction "I6_11") (pintype "input"))
      (node (ref "E46") (pin "12") (pinfunction "I1_12") (pintype "input"))
      (node (ref "E46") (pin "9") (pinfunction "I1_9") (pintype "input"))
    )
    (net (code "16") (name "CC_RUN") (class "Default")
      (node (ref "E26") (pin "12") (pinfunction "O_12") (pintype "output"))
      (node (ref "E37") (pin "9") (pinfunction "I1_9") (pintype "input"))
      (node (ref "E46") (pin "2") (pinfunction "I0_2") (pintype "input"))
      (node (ref "E46") (pin "3") (pinfunction "I1_3") (pintype "input"))
    )
    (net (code "17") (name "CC_R{slash}W") (class "Default")
      (node (ref "E30") (pin "9") (pinfunction "Q_9") (pintype "output"))
      (node (ref "E35") (pin "10") (pinfunction "I1_10") (pintype "input"))
      (node (ref "E38") (pin "9") (pinfunction "I0_9") (pintype "input"))
    )
    (net (code "18") (name "CC_R{slash}~{W}") (class "Default")
      (node (ref "E05") (pin "2") (pinfunction "B0_2") (pintype "input"))
      (node (ref "E30") (pin "8") (pinfunction "~{Q}_8") (pintype "output"))
      (node (ref "E35") (pin "1") (pinfunction "I0_1") (pintype "input"))
    )
    (net (code "19") (name "CC_S{slash}G") (class "Default")
      (node (ref "E30") (pin "5") (pinfunction "Q_5") (pintype "output"))
      (node (ref "E42") (pin "12") (pinfunction "I0_12") (pintype "input"))
      (node (ref "E43") (pin "8") (pinfunction "I0_8") (pintype "input"))
    )
    (net (code "20") (name "CC_S{slash}~{G}") (class "Default")
      (node (ref "E02") (pin "6") (pinfunction "I1_6") (pintype "input"))
      (node (ref "E05") (pin "5") (pinfunction "B1_5") (pintype "input"))
      (node (ref "E30") (pin "6") (pinfunction "~{Q}_6") (pintype "output"))
    )
    (net (code "21") (name "CC_TPG1") (class "Default")
      (node (ref "E14") (pin "12") (pinfunction "D_12") (pintype "input"))
      (node (ref "E14") (pin "5") (pinfunction "Q_5") (pintype "output"))
    )
    (net (code "22") (name "CC_TPG_CLK") (class "Default")
      (node (ref "E01") (pin "13") (pinfunction "I_13") (pintype "input"))
      (node (ref "E04") (pin "5") (pinfunction "Q_5") (pintype "output"))
      (node (ref "E04") (pin "9") (pinfunction "A_9") (pintype "input"))
      (node (ref "E14") (pin "11") (pinfunction "CLK_11") (pintype "input"))
      (node (ref "E14") (pin "3") (pinfunction "CLK_3") (pintype "input"))
    )
    (net (code "23") (name "CC_TT_EN") (class "Default")
      (node (ref "E08") (pin "10") (pinfunction "B_10") (pintype "input"))
      (node (ref "E19") (pin "8") (pinfunction "O_8") (pintype "output"))
    )
    (net (code "24") (name "CC_T{slash}M_EN") (class "Default")
      (node (ref "E02") (pin "12") (pinfunction "I1_12") (pintype "input"))
      (node (ref "E02") (pin "9") (pinfunction "I1_9") (pintype "input"))
      (node (ref "E04") (pin "11") (pinfunction "CLR_11") (pintype "input"))
      (node (ref "E23") (pin "2") (pinfunction "I1_2") (pintype "input"))
      (node (ref "E23") (pin "4") (pinfunction "I1_4") (pintype "input"))
      (node (ref "E31") (pin "5") (pinfunction "I_5") (pintype "input"))
      (node (ref "E43") (pin "6") (pinfunction "I1_6") (pintype "input"))
      (node (ref "E46") (pin "5") (pinfunction "I0_5") (pintype "input"))
      (node (ref "R16") (pin "1") (pinfunction "1_1") (pintype "passive"))
      (node (ref "WTM") (pin "1") (pinfunction "P_1") (pintype "passive"))
    )
    (net (code "25") (name "CC_T{slash}~{M_EN}") (class "Default")
      (node (ref "E03") (pin "10") (pinfunction "PRE_10") (pintype "input"))
      (node (ref "E31") (pin "6") (pinfunction "O_6") (pintype "output"))
      (node (ref "E43") (pin "2") (pinfunction "I0_2") (pintype "input"))
    )
    (net (code "26") (name "CC_UNIT") (class "Default")
      (node (ref "E34") (pin "9") (pinfunction "Q_9") (pintype "output"))
      (node (ref "E39") (pin "11") (pinfunction "I_11") (pintype "input"))
      (node (ref "E42") (pin "8") (pinfunction "I0_8") (pintype "input"))
    )
    (net (code "27") (name "CC_UTS") (class "Default")
      (node (ref "E03") (pin "9") (pinfunction "Q_9") (pintype "output"))
      (node (ref "E09") (pin "1") (pinfunction "CLR_1") (pintype "input"))
      (node (ref "E21") (pin "13") (pinfunction "S_13") (pintype "input"))
      (node (ref "E29") (pin "13") (pinfunction "S_13") (pintype "input"))
      (node (ref "E38") (pin "5") (pinfunction "I1_5") (pintype "input"))
    )
    (net (code "28") (name "CC_WRT_OK") (class "Default")
      (node (ref "E26") (pin "2") (pinfunction "O_2") (pintype "output"))
      (node (ref "E46") (pin "6") (pinfunction "I1_6") (pintype "input"))
    )
    (net (code "29") (name "CON_ALL_HALT") (class "Default")
      (node (ref "E46") (pin "1") (pinfunction "O_1") (pintype "open_collector"))
      (node (ref "J1") (pin "RR") (pinfunction "36_RR") (pintype "bidirectional"))
    )
    (net (code "30") (name "DATA00") (class "Default")
      (node (ref "E05") (pin "12") (pinfunction "F2_12") (pintype "open_collector"))
      (node (ref "E17") (pin "10") (pinfunction "I1_10") (pintype "input"))
      (node (ref "EDGE$") (pin "AR1") (pinfunction "1_AR1") (pintype "bidirectional"))
    )
    (net (code "31") (name "DATA01") (class "Default")
      (node (ref "E05") (pin "13") (pinfunction "F3_13") (pintype "open_collector"))
      (node (ref "E12") (pin "9") (pinfunction "I0_9") (pintype "input"))
      (node (ref "EDGE$") (pin "AS1") (pinfunction "1_AS1") (pintype "bidirectional"))
    )
    (net (code "32") (name "DATA02") (class "Default")
      (node (ref "E05") (pin "4") (pinfunction "F1_4") (pintype "open_collector"))
      (node (ref "E07") (pin "10") (pinfunction "I1_10") (pintype "input"))
      (node (ref "EDGE$") (pin "AU1") (pinfunction "1_AU1") (pintype "bidirectional"))
    )
    (net (code "33") (name "DATA03") (class "Default")
      (node (ref "E05") (pin "3") (pinfunction "F0_3") (pintype "open_collector"))
      (node (ref "E17") (pin "12") (pinfunction "I1_12") (pintype "input"))
      (node (ref "EDGE$") (pin "AV1") (pinfunction "1_AV1") (pintype "bidirectional"))
    )
    (net (code "34") (name "DATA04") (class "Default")
      (node (ref "E10") (pin "12") (pinfunction "F2_12") (pintype "open_collector"))
      (node (ref "E12") (pin "12") (pinfunction "I1_12") (pintype "input"))
      (node (ref "EDGE$") (pin "BR1") (pinfunction "1_BR1") (pintype "bidirectional"))
    )
    (net (code "35") (name "DATA05") (class "Default")
      (node (ref "E07") (pin "12") (pinfunction "I1_12") (pintype "input"))
      (node (ref "E10") (pin "13") (pinfunction "F3_13") (pintype "open_collector"))
      (node (ref "EDGE$") (pin "BS1") (pinfunction "1_BS1") (pintype "bidirectional"))
    )
    (net (code "36") (name "DATA06") (class "Default")
      (node (ref "E10") (pin "4") (pinfunction "F1_4") (pintype "open_collector"))
      (node (ref "E17") (pin "5") (pinfunction "I1_5") (pintype "input"))
      (node (ref "EDGE$") (pin "BU1") (pinfunction "1_BU1") (pintype "bidirectional"))
    )
    (net (code "37") (name "DATA07") (class "Default")
      (node (ref "E10") (pin "3") (pinfunction "F0_3") (pintype "open_collector"))
      (node (ref "E12") (pin "5") (pinfunction "I1_5") (pintype "input"))
      (node (ref "EDGE$") (pin "BV1") (pinfunction "1_BV1") (pintype "bidirectional"))
    )
    (net (code "38") (name "DATA08") (class "Default")
      (node (ref "E07") (pin "4") (pinfunction "I0_4") (pintype "input"))
      (node (ref "E15") (pin "12") (pinfunction "F2_12") (pintype "open_collector"))
      (node (ref "EDGE$") (pin "DR1") (pinfunction "1_DR1") (pintype "bidirectional"))
    )
    (net (code "39") (name "DATA09") (class "Default")
      (node (ref "E15") (pin "13") (pinfunction "F3_13") (pintype "open_collector"))
      (node (ref "E17") (pin "7") (pinfunction "I1_7") (pintype "input"))
      (node (ref "EDGE$") (pin "DS1") (pinfunction "1_DS1") (pintype "bidirectional"))
    )
    (net (code "40") (name "DATA10") (class "Default")
      (node (ref "E12") (pin "7") (pinfunction "I1_7") (pintype "input"))
      (node (ref "E15") (pin "4") (pinfunction "F1_4") (pintype "open_collector"))
      (node (ref "EDGE$") (pin "DU1") (pinfunction "1_DU1") (pintype "bidirectional"))
    )
    (net (code "41") (name "DATA11") (class "Default")
      (node (ref "E07") (pin "7") (pinfunction "I1_7") (pintype "input"))
      (node (ref "E15") (pin "3") (pinfunction "F0_3") (pintype "open_collector"))
      (node (ref "EDGE$") (pin "DV1") (pinfunction "1_DV1") (pintype "bidirectional"))
    )
    (net (code "42") (name "DF_COMP_WD") (class "Default")
      (node (ref "E18") (pin "12") (pinfunction "I0_12") (pintype "input"))
      (node (ref "E18") (pin "5") (pinfunction "I0_5") (pintype "input"))
      (node (ref "E18") (pin "9") (pinfunction "I1_9") (pintype "input"))
      (node (ref "E22") (pin "13") (pinfunction "I1_13") (pintype "input"))
      (node (ref "E22") (pin "3") (pinfunction "O_3") (pintype "output"))
    )
    (net (code "43") (name "DF_DB00") (class "Default")
      (node (ref "E16") (pin "14") (pinfunction "I3_14") (pintype "input"))
      (node (ref "E17") (pin "14") (pinfunction "O_14") (pintype "output"))
      (node (ref "E34") (pin "12") (pinfunction "D_12") (pintype "input"))
      (node (ref "E42") (pin "9") (pinfunction "I1_9") (pintype "input"))
    )
    (net (code "44") (name "DF_DB01") (class "Default")
      (node (ref "E11") (pin "14") (pinfunction "I3_14") (pintype "input"))
      (node (ref "E12") (pin "14") (pinfunction "O_14") (pintype "output"))
      (node (ref "E18") (pin "2") (pinfunction "I1_2") (pintype "input"))
      (node (ref "E34") (pin "2") (pinfunction "D_2") (pintype "input"))
    )
    (net (code "45") (name "DF_DB02") (class "Default")
      (node (ref "E06") (pin "14") (pinfunction "I3_14") (pintype "input"))
      (node (ref "E07") (pin "14") (pinfunction "O_14") (pintype "output"))
      (node (ref "E30") (pin "2") (pinfunction "D_2") (pintype "input"))
      (node (ref "E42") (pin "13") (pinfunction "I1_13") (pintype "input"))
    )
    (net (code "46") (name "DF_DB03") (class "Default")
      (node (ref "E16") (pin "15") (pinfunction "I2_15") (pintype "input"))
      (node (ref "E17") (pin "13") (pinfunction "O_13") (pintype "output"))
      (node (ref "E30") (pin "12") (pinfunction "D_12") (pintype "input"))
    )
    (net (code "47") (name "DF_SEL_ER") (class "Default")
      (node (ref "E32") (pin "12") (pinfunction "O_12") (pintype "output"))
      (node (ref "E37") (pin "6") (pinfunction "I1_6") (pintype "input"))
    )
    (net (code "48") (name "DF_TIME_ER") (class "Default")
      (node (ref "E27") (pin "13") (pinfunction "I2_13") (pintype "input"))
      (node (ref "E35") (pin "6") (pinfunction "O_6") (pintype "output"))
      (node (ref "E37") (pin "5") (pinfunction "I0_5") (pintype "input"))
      (node (ref "E41") (pin "2") (pinfunction "I0_2") (pintype "input"))
    )
    (net (code "49") (name "F{slash}~{R}") (class "Default")
      (node (ref "E39") (pin "8") (pinfunction "O_8") (pintype "open_collector"))
      (node (ref "J1") (pin "TT") (pinfunction "38_TT") (pintype "bidirectional"))
    )
    (net (code "50") (name "GND") (class "Default")
      (node (ref "C1") (pin "2") (pinfunction "2_2") (pintype "passive"))
      (node (ref "C10") (pin "2") (pinfunction "2_2") (pintype "passive"))
      (node (ref "C11") (pin "2") (pinfunction "2_2") (pintype "passive"))
      (node (ref "C12") (pin "2") (pinfunction "2_2") (pintype "passive"))
      (node (ref "C13") (pin "2") (pinfunction "2_2") (pintype "passive"))
      (node (ref "C14") (pin "2") (pinfunction "2_2") (pintype "passive"))
      (node (ref "C15") (pin "2") (pinfunction "2_2") (pintype "passive"))
      (node (ref "C16") (pin "2") (pinfunction "2_2") (pintype "passive"))
      (node (ref "C17") (pin "2") (pinfunction "2_2") (pintype "passive"))
      (node (ref "C18") (pin "2") (pinfunction "2_2") (pintype "passive"))
      (node (ref "C19") (pin "2") (pinfunction "2_2") (pintype "passive"))
      (node (ref "C2") (pin "2") (pinfunction "2_2") (pintype "passive"))
      (node (ref "C20") (pin "2") (pinfunction "2_2") (pintype "passive"))
      (node (ref "C21") (pin "2") (pinfunction "2_2") (pintype "passive"))
      (node (ref "C22") (pin "2") (pinfunction "2_2") (pintype "passive"))
      (node (ref "C23") (pin "2") (pinfunction "2_2") (pintype "passive"))
      (node (ref "C24") (pin "2") (pinfunction "2_2") (pintype "passive"))
      (node (ref "C25") (pin "2") (pinfunction "2_2") (pintype "passive"))
      (node (ref "C26") (pin "2") (pinfunction "2_2") (pintype "passive"))
      (node (ref "C27") (pin "2") (pinfunction "2_2") (pintype "passive"))
      (node (ref "C28") (pin "2") (pinfunction "2_2") (pintype "passive"))
      (node (ref "C29") (pin "2") (pinfunction "2_2") (pintype "passive"))
      (node (ref "C3") (pin "2") (pinfunction "2_2") (pintype "passive"))
      (node (ref "C30") (pin "2") (pinfunction "2_2") (pintype "passive"))
      (node (ref "C31") (pin "2") (pinfunction "2_2") (pintype "passive"))
      (node (ref "C32") (pin "2") (pinfunction "2_2") (pintype "passive"))
      (node (ref "C33") (pin "2") (pinfunction "2_2") (pintype "passive"))
      (node (ref "C34") (pin "-") (pinfunction "-_-") (pintype "passive"))
      (node (ref "C35") (pin "-") (pinfunction "-_-") (pintype "passive"))
      (node (ref "C4") (pin "2") (pinfunction "2_2") (pintype "passive"))
      (node (ref "C40") (pin "2") (pinfunction "2_2") (pintype "passive"))
      (node (ref "C41") (pin "1") (pinfunction "1_1") (pintype "passive"))
      (node (ref "C42") (pin "1") (pinfunction "1_1") (pintype "passive"))
      (node (ref "C43") (pin "2") (pinfunction "2_2") (pintype "passive"))
      (node (ref "C44") (pin "1") (pinfunction "1_1") (pintype "passive"))
      (node (ref "C45") (pin "2") (pinfunction "2_2") (pintype "passive"))
      (node (ref "C46") (pin "-") (pinfunction "-_-") (pintype "passive"))
      (node (ref "C47") (pin "2") (pinfunction "2_2") (pintype "passive"))
      (node (ref "C48") (pin "1") (pinfunction "1_1") (pintype "passive"))
      (node (ref "C5") (pin "2") (pinfunction "2_2") (pintype "passive"))
      (node (ref "C6") (pin "2") (pinfunction "2_2") (pintype "passive"))
      (node (ref "C7") (pin "2") (pinfunction "2_2") (pintype "passive"))
      (node (ref "C8") (pin "2") (pinfunction "2_2") (pintype "passive"))
      (node (ref "C9") (pin "2") (pinfunction "2_2") (pintype "passive"))
      (node (ref "D2") (pin "A") (pinfunction "A_A") (pintype "passive"))
      (node (ref "E04") (pin "1") (pinfunction "A_1") (pintype "input"))
      (node (ref "E08") (pin "1") (pinfunction "A_1") (pintype "input"))
      (node (ref "E08") (pin "9") (pinfunction "A_9") (pintype "input"))
      (node (ref "E20") (pin "10") (pinfunction "I1_10") (pintype "input"))
      (node (ref "E20") (pin "12") (pinfunction "I1_12") (pintype "input"))
      (node (ref "E25") (pin "7") (pinfunction "7_7") (pintype "passive"))
      (node (ref "E28") (pin "10") (pinfunction "I1_10") (pintype "input"))
      (node (ref "E28") (pin "4") (pinfunction "I0_4") (pintype "input"))
      (node (ref "E28") (pin "7") (pinfunction "I1_7") (pintype "input"))
      (node (ref "EDGE$") (pin "AC2") (pinfunction "1_AC2") (pintype "bidirectional"))
      (node (ref "EDGE$") (pin "AF1") (pinfunction "1_AF1") (pintype "bidirectional"))
      (node (ref "EDGE$") (pin "AF2") (pinfunction "1_AF2") (pintype "bidirectional"))
      (node (ref "EDGE$") (pin "AN1") (pinfunction "1_AN1") (pintype "bidirectional"))
      (node (ref "EDGE$") (pin "AN2") (pinfunction "1_AN2") (pintype "bidirectional"))
      (node (ref "EDGE$") (pin "AT1") (pinfunction "1_AT1") (pintype "bidirectional"))
      (node (ref "EDGE$") (pin "AT2") (pinfunction "1_AT2") (pintype "bidirectional"))
      (node (ref "EDGE$") (pin "BC1") (pinfunction "1_BC1") (pintype "bidirectional"))
      (node (ref "EDGE$") (pin "BC2") (pinfunction "1_BC2") (pintype "bidirectional"))
      (node (ref "EDGE$") (pin "BF1") (pinfunction "1_BF1") (pintype "bidirectional"))
      (node (ref "EDGE$") (pin "BF2") (pinfunction "1_BF2") (pintype "bidirectional"))
      (node (ref "EDGE$") (pin "BN2") (pinfunction "1_BN2") (pintype "bidirectional"))
      (node (ref "EDGE$") (pin "BT1") (pinfunction "1_BT1") (pintype "bidirectional"))
      (node (ref "EDGE$") (pin "BT2") (pinfunction "1_BT2") (pintype "bidirectional"))
      (node (ref "EDGE$") (pin "CC1") (pinfunction "1_CC1") (pintype "bidirectional"))
      (node (ref "EDGE$") (pin "CC2") (pinfunction "1_CC2") (pintype "bidirectional"))
      (node (ref "EDGE$") (pin "CF1") (pinfunction "1_CF1") (pintype "bidirectional"))
      (node (ref "EDGE$") (pin "CF2") (pinfunction "1_CF2") (pintype "bidirectional"))
      (node (ref "EDGE$") (pin "CN1") (pinfunction "1_CN1") (pintype "bidirectional"))
      (node (ref "EDGE$") (pin "CN2") (pinfunction "1_CN2") (pintype "bidirectional"))
      (node (ref "EDGE$") (pin "CT1") (pinfunction "1_CT1") (pintype "bidirectional"))
      (node (ref "EDGE$") (pin "CT2") (pinfunction "1_CT2") (pintype "bidirectional"))
      (node (ref "EDGE$") (pin "DC1") (pinfunction "1_DC1") (pintype "bidirectional"))
      (node (ref "EDGE$") (pin "DC2") (pinfunction "1_DC2") (pintype "bidirectional"))
      (node (ref "EDGE$") (pin "DF1") (pinfunction "1_DF1") (pintype "bidirectional"))
      (node (ref "EDGE$") (pin "DF2") (pinfunction "1_DF2") (pintype "bidirectional"))
      (node (ref "EDGE$") (pin "DN1") (pinfunction "1_DN1") (pintype "bidirectional"))
      (node (ref "EDGE$") (pin "DN2") (pinfunction "1_DN2") (pintype "bidirectional"))
      (node (ref "EDGE$") (pin "DT1") (pinfunction "1_DT1") (pintype "bidirectional"))
      (node (ref "EDGE$") (pin "DT2") (pinfunction "1_DT2") (pintype "bidirectional"))
      (node (ref "J1") (pin "A") (pinfunction "1_A") (pintype "bidirectional"))
      (node (ref "J1") (pin "AA") (pinfunction "23_AA") (pintype "bidirectional"))
      (node (ref "J1") (pin "B") (pinfunction "2_B") (pintype "bidirectional"))
      (node (ref "J1") (pin "C") (pinfunction "3_C") (pintype "bidirectional"))
      (node (ref "J1") (pin "CC") (pinfunction "25_CC") (pintype "bidirectional"))
      (node (ref "J1") (pin "E") (pinfunction "5_E") (pintype "bidirectional"))
      (node (ref "J1") (pin "EE") (pinfunction "27_EE") (pintype "bidirectional"))
      (node (ref "J1") (pin "H") (pinfunction "7_H") (pintype "bidirectional"))
      (node (ref "J1") (pin "HH") (pinfunction "29_HH") (pintype "bidirectional"))
      (node (ref "J1") (pin "K") (pinfunction "9_K") (pintype "bidirectional"))
      (node (ref "J1") (pin "KK") (pinfunction "31_KK") (pintype "bidirectional"))
      (node (ref "J1") (pin "M") (pinfunction "11_M") (pintype "bidirectional"))
      (node (ref "J1") (pin "MM") (pinfunction "33_MM") (pintype "bidirectional"))
      (node (ref "J1") (pin "P") (pinfunction "13_P") (pintype "bidirectional"))
      (node (ref "J1") (pin "PP") (pinfunction "35_PP") (pintype "bidirectional"))
      (node (ref "J1") (pin "S") (pinfunction "15_S") (pintype "bidirectional"))
      (node (ref "J1") (pin "SS") (pinfunction "37_SS") (pintype "bidirectional"))
      (node (ref "J1") (pin "U") (pinfunction "17_U") (pintype "bidirectional"))
      (node (ref "J1") (pin "UU") (pinfunction "39_UU") (pintype "bidirectional"))
      (node (ref "J1") (pin "VV") (pinfunction "40_VV") (pintype "bidirectional"))
      (node (ref "J1") (pin "W") (pinfunction "19_W") (pintype "bidirectional"))
      (node (ref "J1") (pin "Y") (pinfunction "21_Y") (pintype "bidirectional"))
      (node (ref "Q4") (pin "3") (pinfunction "C_3") (pintype "passive"))
      (node (ref "Q5") (pin "3") (pinfunction "C_3") (pintype "passive"))
      (node (ref "R36") (pin "2") (pinfunction "2_2") (pintype "passive"))
      (node (ref "R37") (pin "2") (pinfunction "2_2") (pintype "passive"))
      (node (ref "WTM") (pin "2") (pinfunction "S_2") (pintype "passive"))
    )
    (net (code "51") (name "INITIALIZE") (class "Default")
      (node (ref "E28") (pin "5") (pinfunction "I1_5") (pintype "input"))
      (node (ref "EDGE$") (pin "CR1") (pinfunction "1_CR1") (pintype "bidirectional"))
    )
    (net (code "52") (name "INTERNAL_IO") (class "Default")
      (node (ref "E33") (pin "4") (pinfunction "O_4") (pintype "open_collector"))
      (node (ref "EDGE$") (pin "CL1") (pinfunction "1_CL1") (pintype "bidirectional"))
    )
    (net (code "53") (name "IO_PAUSE") (class "Default")
      (node (ref "E28") (pin "9") (pinfunction "I0_9") (pintype "input"))
      (node (ref "EDGE$") (pin "CD1") (pinfunction "1_CD1") (pintype "bidirectional"))
    )
    (net (code "54") (name "MD03") (class "Default")
      (node (ref "E24") (pin "9") (pinfunction "I3_9") (pintype "input"))
      (node (ref "EDGE$") (pin "AP1") (pinfunction "1_AP1") (pintype "bidirectional"))
    )
    (net (code "55") (name "MD04") (class "Default")
      (node (ref "E24") (pin "4") (pinfunction "I0_4") (pintype "input"))
      (node (ref "EDGE$") (pin "BK1") (pinfunction "1_BK1") (pintype "bidirectional"))
    )
    (net (code "56") (name "MD05") (class "Default")
      (node (ref "E24") (pin "5") (pinfunction "I1_5") (pintype "input"))
      (node (ref "EDGE$") (pin "BL1") (pinfunction "1_BL1") (pintype "bidirectional"))
    )
    (net (code "57") (name "MD06") (class "Default")
      (node (ref "E24") (pin "6") (pinfunction "I2_6") (pintype "input"))
      (node (ref "EDGE$") (pin "BM1") (pinfunction "1_BM1") (pintype "bidirectional"))
    )
    (net (code "58") (name "MD07") (class "Default")
      (node (ref "E20") (pin "5") (pinfunction "I1_5") (pintype "input"))
      (node (ref "EDGE$") (pin "BP1") (pinfunction "1_BP1") (pintype "bidirectional"))
      (node (ref "W2W1") (pin "1") (pinfunction "1_1") (pintype "passive"))
    )
    (net (code "59") (name "MD08") (class "Default")
      (node (ref "E20") (pin "6") (pinfunction "I0_6") (pintype "input"))
      (node (ref "EDGE$") (pin "DK1") (pinfunction "1_DK1") (pintype "bidirectional"))
      (node (ref "W4W3") (pin "1") (pinfunction "1_1") (pintype "passive"))
    )
    (net (code "60") (name "MD09") (class "Default")
      (node (ref "E44") (pin "7") (pinfunction "I1_7") (pintype "input"))
      (node (ref "EDGE$") (pin "DL1") (pinfunction "1_DL1") (pintype "bidirectional"))
    )
    (net (code "61") (name "MD10") (class "Default")
      (node (ref "E44") (pin "9") (pinfunction "I0_9") (pintype "input"))
      (node (ref "EDGE$") (pin "DM1") (pinfunction "1_DM1") (pintype "bidirectional"))
    )
    (net (code "62") (name "MD11") (class "Default")
      (node (ref "E44") (pin "11") (pinfunction "I0_11") (pintype "input"))
      (node (ref "EDGE$") (pin "DP1") (pinfunction "1_DP1") (pintype "bidirectional"))
    )
    (net (code "63") (name "N$36") (class "Default")
      (node (ref "E36") (pin "11") (pinfunction "QD_11") (pintype "output"))
      (node (ref "E37") (pin "3") (pinfunction "I1_3") (pintype "input"))
      (node (ref "E41") (pin "12") (pinfunction "I1_12") (pintype "input"))
    )
    (net (code "64") (name "ND0") (class "Default")
      (node (ref "E39") (pin "12") (pinfunction "O_12") (pintype "open_collector"))
      (node (ref "J1") (pin "FF") (pinfunction "28_FF") (pintype "bidirectional"))
    )
    (net (code "65") (name "ND1") (class "Default")
      (node (ref "E39") (pin "4") (pinfunction "O_4") (pintype "open_collector"))
      (node (ref "J1") (pin "DD") (pinfunction "26_DD") (pintype "bidirectional"))
    )
    (net (code "66") (name "ND2") (class "Default")
      (node (ref "E39") (pin "2") (pinfunction "O_2") (pintype "open_collector"))
      (node (ref "J1") (pin "X") (pinfunction "20_X") (pintype "bidirectional"))
    )
    (net (code "67") (name "Net-(D2-PadC)") (class "Default")
      (node (ref "D2") (pin "C") (pinfunction "C_C") (pintype "passive"))
      (node (ref "D3") (pin "A") (pinfunction "A_A") (pintype "passive"))
    )
    (net (code "68") (name "Net-(D4-PadC)") (class "Default")
      (node (ref "D4") (pin "C") (pinfunction "C_C") (pintype "passive"))
      (node (ref "D6") (pin "A") (pinfunction "A_A") (pintype "passive"))
    )
    (net (code "69") (name "Net-(D7-PadC)") (class "Default")
      (node (ref "D7") (pin "C") (pinfunction "C_C") (pintype "passive"))
      (node (ref "D8") (pin "C") (pinfunction "C_C") (pintype "passive"))
      (node (ref "R39") (pin "2") (pinfunction "2_2") (pintype "passive"))
    )
    (net (code "70") (name "Net-(D10-PadC)") (class "Default")
      (node (ref "D10") (pin "C") (pinfunction "C_C") (pintype "passive"))
      (node (ref "D9") (pin "C") (pinfunction "C_C") (pintype "passive"))
      (node (ref "R40") (pin "2") (pinfunction "2_2") (pintype "passive"))
    )
    (net (code "71") (name "Net-(E01F-O)") (class "Default")
      (node (ref "E01") (pin "12") (pinfunction "O_12") (pintype "output"))
      (node (ref "R25") (pin "2") (pinfunction "2_2") (pintype "passive"))
    )
    (net (code "72") (name "Net-(E02A-O)") (class "Default")
      (node (ref "E02") (pin "1") (pinfunction "O_1") (pintype "output"))
      (node (ref "E31") (pin "9") (pinfunction "I_9") (pintype "input"))
    )
    (net (code "73") (name "Net-(E02B-I0)") (class "Default")
      (node (ref "E02") (pin "5") (pinfunction "I0_5") (pintype "input"))
      (node (ref "E03") (pin "6") (pinfunction "~{Q}_6") (pintype "output"))
      (node (ref "E04") (pin "2") (pinfunction "B_2") (pintype "input"))
    )
    (net (code "74") (name "Net-(E02B-O)") (class "Default")
      (node (ref "E02") (pin "4") (pinfunction "O_4") (pintype "output"))
      (node (ref "E03") (pin "12") (pinfunction "D_12") (pintype "input"))
      (node (ref "E03") (pin "13") (pinfunction "CLR_13") (pintype "input"))
    )
    (net (code "75") (name "Net-(E02C-I0)") (class "Default")
      (node (ref "E02") (pin "8") (pinfunction "I0_8") (pintype "input"))
      (node (ref "E38") (pin "12") (pinfunction "I0_12") (pintype "input"))
      (node (ref "E38") (pin "8") (pinfunction "O_8") (pintype "output"))
    )
    (net (code "76") (name "Net-(E02C-O)") (class "Default")
      (node (ref "E02") (pin "10") (pinfunction "O_10") (pintype "output"))
      (node (ref "E46") (pin "8") (pinfunction "I0_8") (pintype "input"))
    )
    (net (code "77") (name "Net-(E02D-O)") (class "Default")
      (node (ref "E02") (pin "13") (pinfunction "O_13") (pintype "output"))
      (node (ref "E09") (pin "2") (pinfunction "D_2") (pintype "input"))
    )
    (net (code "78") (name "Net-(E03A-CLK)") (class "Default")
      (node (ref "E03") (pin "3") (pinfunction "CLK_3") (pintype "input"))
      (node (ref "E26") (pin "5") (pinfunction "I_5") (pintype "input"))
      (node (ref "E30") (pin "11") (pinfunction "CLK_11") (pintype "input"))
      (node (ref "E30") (pin "3") (pinfunction "CLK_3") (pintype "input"))
      (node (ref "E34") (pin "11") (pinfunction "CLK_11") (pintype "input"))
      (node (ref "E34") (pin "3") (pinfunction "CLK_3") (pintype "input"))
      (node (ref "E37") (pin "13") (pinfunction "O_13") (pintype "output"))
    )
    (net (code "79") (name "Net-(E03A-CLR)") (class "Default")
      (node (ref "E03") (pin "1") (pinfunction "CLR_1") (pintype "input"))
      (node (ref "E04") (pin "3") (pinfunction "CLR_3") (pintype "input"))
      (node (ref "R42") (pin "2") (pinfunction "2_2") (pintype "passive"))
    )
    (net (code "80") (name "Net-(E03A-D)") (class "Default")
      (node (ref "E03") (pin "2") (pinfunction "D_2") (pintype "input"))
      (node (ref "E18") (pin "3") (pinfunction "O_3") (pintype "open_collector"))
      (node (ref "E42") (pin "10") (pinfunction "O_10") (pintype "open_collector"))
      (node (ref "E42") (pin "11") (pinfunction "O_11") (pintype "open_collector"))
      (node (ref "R15") (pin "1") (pinfunction "1_1") (pintype "passive"))
    )
    (net (code "81") (name "Net-(E03A-PRE)") (class "Default")
      (node (ref "E03") (pin "4") (pinfunction "PRE_4") (pintype "input"))
      (node (ref "E43") (pin "12") (pinfunction "I1_12") (pintype "input"))
      (node (ref "E44") (pin "3") (pinfunction "O_3") (pintype "output"))
    )
    (net (code "82") (name "Net-(E03B-CLK)") (class "Default")
      (node (ref "E03") (pin "11") (pinfunction "CLK_11") (pintype "input"))
      (node (ref "E04") (pin "4") (pinfunction "~{Q}_4") (pintype "output"))
    )
    (net (code "83") (name "Net-(E04A-C)") (class "Default")
      (node (ref "C36") (pin "-") (pinfunction "-_-") (pintype "passive"))
      (node (ref "E04") (pin "14") (pinfunction "C_14") (pintype "input"))
    )
    (net (code "84") (name "Net-(E04A-R{slash}C)") (class "Default")
      (node (ref "C36") (pin "+") (pinfunction "+_+") (pintype "passive"))
      (node (ref "E04") (pin "15") (pinfunction "R/C_15") (pintype "input"))
      (node (ref "R17") (pin "1") (pinfunction "1_1") (pintype "passive"))
    )
    (net (code "85") (name "Net-(E04B-C)") (class "Default")
      (node (ref "C39") (pin "2") (pinfunction "2_2") (pintype "passive"))
      (node (ref "E04") (pin "6") (pinfunction "C_6") (pintype "input"))
    )
    (net (code "86") (name "Net-(E04B-R{slash}C)") (class "Default")
      (node (ref "C39") (pin "1") (pinfunction "1_1") (pintype "passive"))
      (node (ref "E04") (pin "7") (pinfunction "R/C_7") (pintype "input"))
      (node (ref "R43") (pin "1") (pinfunction "1_1") (pintype "passive"))
    )
    (net (code "87") (name "Net-(E06A-C)") (class "Default")
      (node (ref "E06") (pin "6") (pinfunction "C_6") (pintype "input"))
      (node (ref "E11") (pin "6") (pinfunction "C_6") (pintype "input"))
      (node (ref "E16") (pin "6") (pinfunction "C_6") (pintype "input"))
      (node (ref "E26") (pin "8") (pinfunction "O_8") (pintype "output"))
    )
    (net (code "88") (name "Net-(E06A-I0)") (class "Default")
      (node (ref "E06") (pin "3") (pinfunction "I0_3") (pintype "input"))
      (node (ref "E07") (pin "2") (pinfunction "O_2") (pintype "output"))
    )
    (net (code "89") (name "Net-(E06A-I1)") (class "Default")
      (node (ref "E06") (pin "2") (pinfunction "I1_2") (pintype "input"))
      (node (ref "E07") (pin "3") (pinfunction "O_3") (pintype "output"))
    )
    (net (code "90") (name "Net-(E06A-I2)") (class "Default")
      (node (ref "E06") (pin "15") (pinfunction "I2_15") (pintype "input"))
      (node (ref "E07") (pin "13") (pinfunction "O_13") (pintype "output"))
    )
    (net (code "91") (name "Net-(E06A-L)") (class "Default")
      (node (ref "E06") (pin "1") (pinfunction "R_1") (pintype "input"))
      (node (ref "E06") (pin "10") (pinfunction "L_10") (pintype "input"))
      (node (ref "E11") (pin "1") (pinfunction "R_1") (pintype "input"))
      (node (ref "E11") (pin "10") (pinfunction "L_10") (pintype "input"))
      (node (ref "E16") (pin "1") (pinfunction "R_1") (pintype "input"))
      (node (ref "E16") (pin "10") (pinfunction "L_10") (pintype "input"))
      (node (ref "R3") (pin "1") (pinfunction "1_1") (pintype "passive"))
    )
    (net (code "92") (name "Net-(E08A-B)") (class "Default")
      (node (ref "E08") (pin "2") (pinfunction "B_2") (pintype "input"))
      (node (ref "E08") (pin "5") (pinfunction "Q_5") (pintype "output"))
    )
    (net (code "93") (name "Net-(E08A-C)") (class "Default")
      (node (ref "C38") (pin "2") (pinfunction "2_2") (pintype "passive"))
      (node (ref "E08") (pin "14") (pinfunction "C_14") (pintype "input"))
    )
    (net (code "94") (name "Net-(E08A-CLR)") (class "Default")
      (node (ref "E08") (pin "11") (pinfunction "CLR_11") (pintype "input"))
      (node (ref "E08") (pin "3") (pinfunction "CLR_3") (pintype "input"))
      (node (ref "E09") (pin "10") (pinfunction "PRE_10") (pintype "input"))
      (node (ref "E09") (pin "13") (pinfunction "CLR_13") (pintype "input"))
      (node (ref "E09") (pin "4") (pinfunction "PRE_4") (pintype "input"))
      (node (ref "E14") (pin "1") (pinfunction "CLR_1") (pintype "input"))
      (node (ref "E14") (pin "10") (pinfunction "PRE_10") (pintype "input"))
      (node (ref "E14") (pin "13") (pinfunction "CLR_13") (pintype "input"))
      (node (ref "E14") (pin "4") (pinfunction "PRE_4") (pintype "input"))
      (node (ref "R22") (pin "2") (pinfunction "2_2") (pintype "passive"))
    )
    (net (code "95") (name "Net-(E08A-R{slash}C)") (class "Default")
      (node (ref "C38") (pin "1") (pinfunction "1_1") (pintype "passive"))
      (node (ref "E08") (pin "15") (pinfunction "R/C_15") (pintype "input"))
      (node (ref "R24") (pin "1") (pinfunction "1_1") (pintype "passive"))
    )
    (net (code "96") (name "Net-(E08B-C)") (class "Default")
      (node (ref "C37") (pin "2") (pinfunction "2_2") (pintype "passive"))
      (node (ref "E08") (pin "6") (pinfunction "C_6") (pintype "input"))
    )
    (net (code "97") (name "Net-(E08B-R{slash}C)") (class "Default")
      (node (ref "C37") (pin "1") (pinfunction "1_1") (pintype "passive"))
      (node (ref "E08") (pin "7") (pinfunction "R/C_7") (pintype "input"))
      (node (ref "R23") (pin "1") (pinfunction "1_1") (pintype "passive"))
    )
    (net (code "98") (name "Net-(E08B-~{Q})") (class "Default")
      (node (ref "E08") (pin "12") (pinfunction "~{Q}_12") (pintype "output"))
      (node (ref "E09") (pin "11") (pinfunction "CLK_11") (pintype "input"))
      (node (ref "E09") (pin "3") (pinfunction "CLK_3") (pintype "input"))
      (node (ref "E19") (pin "9") (pinfunction "I0_9") (pintype "input"))
    )
    (net (code "99") (name "Net-(E09A-Q)") (class "Default")
      (node (ref "E09") (pin "5") (pinfunction "Q_5") (pintype "output"))
      (node (ref "E23") (pin "9") (pinfunction "I0_9") (pintype "input"))
      (node (ref "E27") (pin "9") (pinfunction "I0_9") (pintype "input"))
    )
    (net (code "100") (name "Net-(E09B-D)") (class "Default")
      (node (ref "E09") (pin "12") (pinfunction "D_12") (pintype "input"))
      (node (ref "E09") (pin "8") (pinfunction "~{Q}_8") (pintype "output"))
      (node (ref "E23") (pin "11") (pinfunction "I2_11") (pintype "input"))
    )
    (net (code "101") (name "Net-(E10A-B3)") (class "Default")
      (node (ref "E10") (pin "14") (pinfunction "B3_14") (pintype "input"))
      (node (ref "E37") (pin "4") (pinfunction "O_4") (pintype "output"))
    )
    (net (code "102") (name "Net-(E11A-I0)") (class "Default")
      (node (ref "E11") (pin "3") (pinfunction "I0_3") (pintype "input"))
      (node (ref "E12") (pin "2") (pinfunction "O_2") (pintype "output"))
    )
    (net (code "103") (name "Net-(E11A-I1)") (class "Default")
      (node (ref "E11") (pin "2") (pinfunction "I1_2") (pintype "input"))
      (node (ref "E12") (pin "3") (pinfunction "O_3") (pintype "output"))
    )
    (net (code "104") (name "Net-(E11A-I2)") (class "Default")
      (node (ref "E11") (pin "15") (pinfunction "I2_15") (pintype "input"))
      (node (ref "E12") (pin "13") (pinfunction "O_13") (pintype "output"))
    )
    (net (code "105") (name "Net-(E13A-C12)") (class "Default")
      (node (ref "E13") (pin "13") (pinfunction "C12_13") (pintype "input"))
      (node (ref "E13") (pin "4") (pinfunction "C34_4") (pintype "input"))
      (node (ref "E31") (pin "12") (pinfunction "O_12") (pintype "output"))
    )
    (net (code "106") (name "Net-(E13A-~{Q1})") (class "Default")
      (node (ref "E13") (pin "1") (pinfunction "~{Q1}_1") (pintype "output"))
      (node (ref "E18") (pin "13") (pinfunction "I1_13") (pintype "input"))
    )
    (net (code "107") (name "Net-(E13A-~{Q3})") (class "Default")
      (node (ref "E13") (pin "11") (pinfunction "~{Q3}_11") (pintype "output"))
      (node (ref "E18") (pin "6") (pinfunction "I1_6") (pintype "input"))
    )
    (net (code "108") (name "Net-(E13A-~{Q4})") (class "Default")
      (node (ref "E13") (pin "8") (pinfunction "~{Q4}_8") (pintype "output"))
      (node (ref "E18") (pin "8") (pinfunction "I0_8") (pintype "input"))
    )
    (net (code "109") (name "Net-(E14A-D)") (class "Default")
      (node (ref "E14") (pin "2") (pinfunction "D_2") (pintype "input"))
      (node (ref "E14") (pin "8") (pinfunction "~{Q}_8") (pintype "output"))
      (node (ref "E23") (pin "3") (pinfunction "I0_3") (pintype "input"))
      (node (ref "E39") (pin "5") (pinfunction "I_5") (pintype "input"))
    )
    (net (code "110") (name "Net-(E16A-I0)") (class "Default")
      (node (ref "E16") (pin "3") (pinfunction "I0_3") (pintype "input"))
      (node (ref "E17") (pin "2") (pinfunction "O_2") (pintype "output"))
    )
    (net (code "111") (name "Net-(E16A-I1)") (class "Default")
      (node (ref "E16") (pin "2") (pinfunction "I1_2") (pintype "input"))
      (node (ref "E17") (pin "3") (pinfunction "O_3") (pintype "output"))
    )
    (net (code "112") (name "Net-(E18B-O)") (class "Default")
      (node (ref "E18") (pin "4") (pinfunction "O_4") (pintype "open_collector"))
      (node (ref "E39") (pin "13") (pinfunction "I_13") (pintype "input"))
      (node (ref "R10") (pin "1") (pinfunction "1_1") (pintype "passive"))
    )
    (net (code "113") (name "Net-(E18C-O)") (class "Default")
      (node (ref "E18") (pin "10") (pinfunction "O_10") (pintype "open_collector"))
      (node (ref "E39") (pin "3") (pinfunction "I_3") (pintype "input"))
      (node (ref "R9") (pin "1") (pinfunction "1_1") (pintype "passive"))
    )
    (net (code "114") (name "Net-(E18D-O)") (class "Default")
      (node (ref "E18") (pin "11") (pinfunction "O_11") (pintype "open_collector"))
      (node (ref "E39") (pin "1") (pinfunction "I_1") (pintype "input"))
      (node (ref "R8") (pin "1") (pinfunction "1_1") (pintype "passive"))
    )
    (net (code "115") (name "Net-(E19A-I0)") (class "Default")
      (node (ref "E19") (pin "1") (pinfunction "I0_1") (pintype "input"))
      (node (ref "E23") (pin "8") (pinfunction "O_8") (pintype "output"))
    )
    (net (code "116") (name "Net-(E19A-I1)") (class "Default")
      (node (ref "E19") (pin "2") (pinfunction "I1_2") (pintype "input"))
      (node (ref "E23") (pin "12") (pinfunction "O_12") (pintype "output"))
    )
    (net (code "117") (name "Net-(E19B-I0)") (class "Default")
      (node (ref "E19") (pin "4") (pinfunction "I0_4") (pintype "input"))
      (node (ref "E27") (pin "8") (pinfunction "O_8") (pintype "output"))
    )
    (net (code "118") (name "Net-(E19B-I1)") (class "Default")
      (node (ref "E19") (pin "5") (pinfunction "I1_5") (pintype "input"))
      (node (ref "E23") (pin "6") (pinfunction "O_6") (pintype "output"))
    )
    (net (code "119") (name "Net-(E19C-I1)") (class "Default")
      (node (ref "E19") (pin "10") (pinfunction "I1_10") (pintype "input"))
      (node (ref "E43") (pin "1") (pinfunction "O_1") (pintype "open_collector"))
      (node (ref "E43") (pin "4") (pinfunction "O_4") (pintype "open_collector"))
      (node (ref "R21") (pin "1") (pinfunction "1_1") (pintype "passive"))
    )
    (net (code "120") (name "Net-(E19D-I0)") (class "Default")
      (node (ref "E19") (pin "12") (pinfunction "I0_12") (pintype "input"))
      (node (ref "E26") (pin "1") (pinfunction "I_1") (pintype "input"))
      (node (ref "E40") (pin "8") (pinfunction "O_8") (pintype "output"))
    )
    (net (code "121") (name "Net-(E19D-O)") (class "Default")
      (node (ref "E19") (pin "11") (pinfunction "O_11") (pintype "output"))
      (node (ref "E30") (pin "13") (pinfunction "CLR_13") (pintype "input"))
    )
    (net (code "122") (name "Net-(E20A-I0)") (class "Default")
      (node (ref "E20") (pin "4") (pinfunction "I0_4") (pintype "input"))
      (node (ref "E20") (pin "7") (pinfunction "I1_7") (pintype "input"))
      (node (ref "E24") (pin "10") (pinfunction "I4_10") (pintype "input"))
      (node (ref "E28") (pin "14") (pinfunction "O_14") (pintype "output"))
    )
    (net (code "123") (name "Net-(E20A-O)") (class "Default")
      (node (ref "E20") (pin "3") (pinfunction "O_3") (pintype "output"))
      (node (ref "W2W1") (pin "3") (pinfunction "3_3") (pintype "passive"))
    )
    (net (code "124") (name "Net-(E20B-O)") (class "Default")
      (node (ref "E20") (pin "2") (pinfunction "O_2") (pintype "output"))
      (node (ref "W4W3") (pin "3") (pinfunction "3_3") (pintype "passive"))
    )
    (net (code "125") (name "Net-(E21A-C)") (class "Default")
      (node (ref "E21") (pin "6") (pinfunction "C_6") (pintype "input"))
      (node (ref "E22") (pin "6") (pinfunction "O_6") (pintype "output"))
      (node (ref "E29") (pin "6") (pinfunction "C_6") (pintype "input"))
    )
    (net (code "126") (name "Net-(E21A-I0)") (class "Default")
      (node (ref "E21") (pin "1") (pinfunction "R_1") (pintype "input"))
      (node (ref "E21") (pin "10") (pinfunction "L_10") (pintype "input"))
      (node (ref "E21") (pin "14") (pinfunction "I3_14") (pintype "input"))
      (node (ref "E21") (pin "15") (pinfunction "I2_15") (pintype "input"))
      (node (ref "E21") (pin "2") (pinfunction "I1_2") (pintype "input"))
      (node (ref "E21") (pin "3") (pinfunction "I0_3") (pintype "input"))
      (node (ref "E29") (pin "1") (pinfunction "R_1") (pintype "input"))
      (node (ref "E29") (pin "10") (pinfunction "L_10") (pintype "input"))
      (node (ref "E29") (pin "14") (pinfunction "I3_14") (pintype "input"))
      (node (ref "E29") (pin "15") (pinfunction "I2_15") (pintype "input"))
      (node (ref "E29") (pin "2") (pinfunction "I1_2") (pintype "input"))
      (node (ref "E29") (pin "3") (pinfunction "I0_3") (pintype "input"))
      (node (ref "R2") (pin "1") (pinfunction "1_1") (pintype "passive"))
    )
    (net (code "127") (name "Net-(E22A-I0)") (class "Default")
      (node (ref "E22") (pin "1") (pinfunction "I0_1") (pintype "input"))
      (node (ref "E22") (pin "11") (pinfunction "O_11") (pintype "output"))
    )
    (net (code "128") (name "Net-(E22C-I1)") (class "Default")
      (node (ref "E22") (pin "10") (pinfunction "I1_10") (pintype "input"))
      (node (ref "E31") (pin "8") (pinfunction "O_8") (pintype "output"))
    )
    (net (code "129") (name "Net-(E22C-O)") (class "Default")
      (node (ref "E22") (pin "8") (pinfunction "O_8") (pintype "output"))
      (node (ref "E26") (pin "9") (pinfunction "I_9") (pintype "input"))
    )
    (net (code "130") (name "Net-(E24A-I5)") (class "Default")
      (node (ref "E24") (pin "11") (pinfunction "I5_11") (pintype "input"))
      (node (ref "W2W1") (pin "2") (pinfunction "2_2") (pintype "passive"))
    )
    (net (code "131") (name "Net-(E24A-I6)") (class "Default")
      (node (ref "E24") (pin "12") (pinfunction "I6_12") (pintype "input"))
      (node (ref "W4W3") (pin "2") (pinfunction "2_2") (pintype "passive"))
    )
    (net (code "132") (name "Net-(E24A-O)") (class "Default")
      (node (ref "E24") (pin "3") (pinfunction "O_3") (pintype "output"))
      (node (ref "E26") (pin "11") (pinfunction "I_11") (pintype "input"))
      (node (ref "E33") (pin "5") (pinfunction "I0_5") (pintype "input"))
      (node (ref "E33") (pin "6") (pinfunction "I1_6") (pintype "input"))
    )
    (net (code "133") (name "Net-(E26B-I)") (class "Default")
      (node (ref "E26") (pin "3") (pinfunction "I_3") (pintype "input"))
      (node (ref "E43") (pin "10") (pinfunction "O_10") (pintype "open_collector"))
      (node (ref "E43") (pin "11") (pinfunction "I0_11") (pintype "input"))
      (node (ref "R14") (pin "2") (pinfunction "2_2") (pintype "passive"))
    )
    (net (code "134") (name "Net-(E26B-O)") (class "Default")
      (node (ref "E26") (pin "4") (pinfunction "O_4") (pintype "output"))
      (node (ref "E46") (pin "11") (pinfunction "I0_11") (pintype "input"))
    )
    (net (code "135") (name "Net-(E27B-O)") (class "Default")
      (node (ref "E27") (pin "6") (pinfunction "O_6") (pintype "output"))
      (node (ref "E37") (pin "2") (pinfunction "I0_2") (pintype "input"))
      (node (ref "E38") (pin "1") (pinfunction "I0_1") (pintype "input"))
    )
    (net (code "136") (name "Net-(E30A-CLR)") (class "Default")
      (node (ref "E30") (pin "1") (pinfunction "CLR_1") (pintype "input"))
      (node (ref "E37") (pin "10") (pinfunction "O_10") (pintype "output"))
    )
    (net (code "137") (name "Net-(E30A-PRE)") (class "Default")
      (node (ref "E30") (pin "10") (pinfunction "PRE_10") (pintype "input"))
      (node (ref "E30") (pin "4") (pinfunction "PRE_4") (pintype "input"))
      (node (ref "E34") (pin "10") (pinfunction "PRE_10") (pintype "input"))
      (node (ref "E34") (pin "4") (pinfunction "PRE_4") (pintype "input"))
      (node (ref "R12") (pin "1") (pinfunction "1_1") (pintype "passive"))
    )
    (net (code "138") (name "Net-(E31E-I)") (class "Default")
      (node (ref "E31") (pin "11") (pinfunction "I_11") (pintype "input"))
      (node (ref "E37") (pin "1") (pinfunction "O_1") (pintype "output"))
    )
    (net (code "139") (name "Net-(E31E-O)") (class "Default")
      (node (ref "E31") (pin "10") (pinfunction "O_10") (pintype "output"))
      (node (ref "E35") (pin "11") (pinfunction "I2_11") (pintype "input"))
      (node (ref "E35") (pin "13") (pinfunction "I2_13") (pintype "input"))
    )
    (net (code "140") (name "Net-(E32A-O)") (class "Default")
      (node (ref "E32") (pin "2") (pinfunction "O_2") (pintype "output"))
      (node (ref "E41") (pin "11") (pinfunction "I0_11") (pintype "input"))
    )
    (net (code "141") (name "Net-(E32B-O)") (class "Default")
      (node (ref "E32") (pin "4") (pinfunction "O_4") (pintype "output"))
      (node (ref "E41") (pin "9") (pinfunction "I1_9") (pintype "input"))
    )
    (net (code "142") (name "Net-(E32C-O)") (class "Default")
      (node (ref "E32") (pin "6") (pinfunction "O_6") (pintype "output"))
      (node (ref "E41") (pin "3") (pinfunction "I1_3") (pintype "input"))
    )
    (net (code "143") (name "Net-(E32D-I)") (class "Default")
      (node (ref "E32") (pin "9") (pinfunction "I_9") (pintype "input"))
      (node (ref "Q1") (pin "3") (pinfunction "C_3") (pintype "passive"))
      (node (ref "R27") (pin "1") (pinfunction "1_1") (pintype "passive"))
    )
    (net (code "144") (name "Net-(E33A-I0)") (class "Default")
      (node (ref "E33") (pin "2") (pinfunction "I0_2") (pintype "input"))
      (node (ref "E41") (pin "5") (pinfunction "I0_5") (pintype "input"))
      (node (ref "E41") (pin "6") (pinfunction "I1_6") (pintype "input"))
      (node (ref "E44") (pin "2") (pinfunction "O_2") (pintype "output"))
      (node (ref "E45") (pin "1") (pinfunction "C_1") (pintype "input"))
    )
    (net (code "145") (name "Net-(E33A-I1)") (class "Default")
      (node (ref "E33") (pin "3") (pinfunction "I1_3") (pintype "input"))
      (node (ref "E44") (pin "14") (pinfunction "O_14") (pintype "output"))
      (node (ref "E45") (pin "14") (pinfunction "B_14") (pintype "input"))
    )
    (net (code "146") (name "Net-(E33C-I0)") (class "Default")
      (node (ref "E33") (pin "8") (pinfunction "I0_8") (pintype "input"))
      (node (ref "E33") (pin "9") (pinfunction "I1_9") (pintype "input"))
      (node (ref "E41") (pin "4") (pinfunction "O_4") (pintype "open_collector"))
    )
    (net (code "147") (name "Net-(E33C-O)") (class "Default")
      (node (ref "E33") (pin "10") (pinfunction "O_10") (pintype "open_collector"))
      (node (ref "E33") (pin "11") (pinfunction "I0_11") (pintype "input"))
    )
    (net (code "148") (name "Net-(E35A-O)") (class "Default")
      (node (ref "E35") (pin "12") (pinfunction "O_12") (pintype "output"))
      (node (ref "E35") (pin "3") (pinfunction "I0_3") (pintype "input"))
    )
    (net (code "149") (name "Net-(E35B-I1)") (class "Default")
      (node (ref "E35") (pin "4") (pinfunction "I1_4") (pintype "input"))
      (node (ref "E35") (pin "8") (pinfunction "O_8") (pintype "output"))
    )
    (net (code "150") (name "Net-(E36A-QA)") (class "Default")
      (node (ref "E36") (pin "12") (pinfunction "QA_12") (pintype "output"))
      (node (ref "E41") (pin "8") (pinfunction "I0_8") (pintype "input"))
    )
    (net (code "151") (name "Net-(E36A-R0(1))") (class "Default")
      (node (ref "E36") (pin "2") (pinfunction "R0(1)_2") (pintype "input"))
      (node (ref "E36") (pin "3") (pinfunction "R0(2)_3") (pintype "input"))
      (node (ref "E38") (pin "6") (pinfunction "O_6") (pintype "output"))
    )
    (net (code "152") (name "Net-(E38A-O)") (class "Default")
      (node (ref "E38") (pin "3") (pinfunction "O_3") (pintype "output"))
      (node (ref "E38") (pin "4") (pinfunction "I0_4") (pintype "input"))
    )
    (net (code "153") (name "Net-(E38C-I1)") (class "Default")
      (node (ref "E38") (pin "10") (pinfunction "I1_10") (pintype "input"))
      (node (ref "E38") (pin "11") (pinfunction "O_11") (pintype "output"))
    )
    (net (code "154") (name "Net-(E42A-O)") (class "Default")
      (node (ref "E42") (pin "3") (pinfunction "O_3") (pintype "open_collector"))
      (node (ref "E43") (pin "5") (pinfunction "I0_5") (pintype "input"))
      (node (ref "R20") (pin "1") (pinfunction "1_1") (pintype "passive"))
    )
    (net (code "155") (name "Net-(E42B-O)") (class "Default")
      (node (ref "E42") (pin "4") (pinfunction "O_4") (pintype "open_collector"))
      (node (ref "E43") (pin "3") (pinfunction "I1_3") (pintype "input"))
      (node (ref "R19") (pin "1") (pinfunction "1_1") (pintype "passive"))
    )
    (net (code "156") (name "Net-(E43C-I1)") (class "Default")
      (node (ref "E43") (pin "13") (pinfunction "O_13") (pintype "open_collector"))
      (node (ref "E43") (pin "9") (pinfunction "I1_9") (pintype "input"))
      (node (ref "R13") (pin "2") (pinfunction "2_2") (pintype "passive"))
    )
    (net (code "157") (name "Net-(E44D-O)") (class "Default")
      (node (ref "E44") (pin "13") (pinfunction "O_13") (pintype "output"))
      (node (ref "E45") (pin "15") (pinfunction "A_15") (pintype "input"))
    )
    (net (code "158") (name "Net-(Q1-B)") (class "Default")
      (node (ref "D1") (pin "C") (pinfunction "C_C") (pintype "passive"))
      (node (ref "Q1") (pin "2") (pinfunction "B_2") (pintype "passive"))
      (node (ref "R48") (pin "2") (pinfunction "2_2") (pintype "passive"))
    )
    (net (code "159") (name "Net-(Q1-E)") (class "Default")
      (node (ref "D5") (pin "C") (pinfunction "C_C") (pintype "passive"))
      (node (ref "Q1") (pin "1") (pinfunction "E_1") (pintype "passive"))
      (node (ref "R41") (pin "2") (pinfunction "2_2") (pintype "passive"))
    )
    (net (code "160") (name "Net-(Q2-E)") (class "Default")
      (node (ref "D8") (pin "A") (pinfunction "A_A") (pintype "passive"))
      (node (ref "Q2") (pin "1") (pinfunction "E_1") (pintype "passive"))
    )
    (net (code "161") (name "Net-(Q3-E)") (class "Default")
      (node (ref "D9") (pin "A") (pinfunction "A_A") (pintype "passive"))
      (node (ref "Q3") (pin "1") (pinfunction "E_1") (pintype "passive"))
    )
    (net (code "162") (name "Net-(Q4-E)") (class "Default")
      (node (ref "D7") (pin "A") (pinfunction "A_A") (pintype "passive"))
      (node (ref "Q4") (pin "1") (pinfunction "E_1") (pintype "passive"))
    )
    (net (code "163") (name "Net-(Q5-E)") (class "Default")
      (node (ref "D10") (pin "A") (pinfunction "A_A") (pintype "passive"))
      (node (ref "Q5") (pin "1") (pinfunction "E_1") (pintype "passive"))
    )
    (net (code "164") (name "Net-(R26-A)") (class "Default")
      (node (ref "R26") (pin "1") (pinfunction "A_1") (pintype "passive"))
      (node (ref "R43") (pin "2") (pinfunction "2_2") (pintype "passive"))
    )
    (net (code "165") (name "RD00") (class "Default")
      (node (ref "E16") (pin "4") (pinfunction "D_4") (pintype "input"))
      (node (ref "J1") (pin "D") (pinfunction "4_D") (pintype "bidirectional"))
      (node (ref "R4") (pin "1") (pinfunction "1_1") (pintype "passive"))
    )
    (net (code "166") (name "RD01") (class "Default")
      (node (ref "E11") (pin "4") (pinfunction "D_4") (pintype "input"))
      (node (ref "J1") (pin "L") (pinfunction "10_L") (pintype "bidirectional"))
      (node (ref "R5") (pin "1") (pinfunction "1_1") (pintype "passive"))
    )
    (net (code "167") (name "RD02") (class "Default")
      (node (ref "E06") (pin "4") (pinfunction "D_4") (pintype "input"))
      (node (ref "J1") (pin "V") (pinfunction "18_V") (pintype "bidirectional"))
      (node (ref "R7") (pin "1") (pinfunction "1_1") (pintype "passive"))
    )
    (net (code "168") (name "RMT") (class "Default")
      (node (ref "E21") (pin "4") (pinfunction "D_4") (pintype "input"))
      (node (ref "J1") (pin "F") (pinfunction "6_F") (pintype "bidirectional"))
      (node (ref "R1") (pin "1") (pinfunction "1_1") (pintype "passive"))
    )
    (net (code "169") (name "RUN") (class "Default")
      (node (ref "E20") (pin "9") (pinfunction "I0_9") (pintype "input"))
      (node (ref "EDGE$") (pin "BU2") (pinfunction "1_BU2") (pintype "bidirectional"))
    )
    (net (code "170") (name "SEL_ECHO") (class "Default")
      (node (ref "J1") (pin "N") (pinfunction "12_N") (pintype "bidirectional"))
      (node (ref "Q2") (pin "2") (pinfunction "B_2") (pintype "passive"))
      (node (ref "Q5") (pin "2") (pinfunction "B_2") (pintype "passive"))
      (node (ref "R30") (pin "2") (pinfunction "2_2") (pintype "passive"))
      (node (ref "R31") (pin "2") (pinfunction "2_2") (pintype "passive"))
      (node (ref "R32") (pin "2") (pinfunction "2_2") (pintype "passive"))
      (node (ref "R33") (pin "2") (pinfunction "2_2") (pintype "passive"))
      (node (ref "R34") (pin "2") (pinfunction "2_2") (pintype "passive"))
    )
    (net (code "171") (name "SR00") (class "Default")
      (node (ref "E05") (pin "10") (pinfunction "A2_10") (pintype "input"))
      (node (ref "E13") (pin "6") (pinfunction "D3_6") (pintype "input"))
      (node (ref "E16") (pin "11") (pinfunction "Q3_11") (pintype "output"))
    )
    (net (code "172") (name "SR01") (class "Default")
      (node (ref "E05") (pin "15") (pinfunction "A3_15") (pintype "input"))
      (node (ref "E11") (pin "11") (pinfunction "Q3_11") (pintype "output"))
      (node (ref "E13") (pin "7") (pinfunction "D4_7") (pintype "input"))
    )
    (net (code "173") (name "SR02") (class "Default")
      (node (ref "E05") (pin "6") (pinfunction "A1_6") (pintype "input"))
      (node (ref "E06") (pin "11") (pinfunction "Q3_11") (pintype "output"))
      (node (ref "E13") (pin "2") (pinfunction "D1_2") (pintype "input"))
    )
    (net (code "174") (name "SR03") (class "Default")
      (node (ref "E05") (pin "1") (pinfunction "A0_1") (pintype "input"))
      (node (ref "E16") (pin "9") (pinfunction "Q2_9") (pintype "output"))
    )
    (net (code "175") (name "SR04") (class "Default")
      (node (ref "E10") (pin "10") (pinfunction "A2_10") (pintype "input"))
      (node (ref "E11") (pin "9") (pinfunction "Q2_9") (pintype "output"))
    )
    (net (code "176") (name "SR05") (class "Default")
      (node (ref "E06") (pin "9") (pinfunction "Q2_9") (pintype "output"))
      (node (ref "E10") (pin "15") (pinfunction "A3_15") (pintype "input"))
    )
    (net (code "177") (name "SR06") (class "Default")
      (node (ref "E10") (pin "6") (pinfunction "A1_6") (pintype "input"))
      (node (ref "E16") (pin "7") (pinfunction "Q1_7") (pintype "output"))
    )
    (net (code "178") (name "SR07") (class "Default")
      (node (ref "E10") (pin "1") (pinfunction "A0_1") (pintype "input"))
      (node (ref "E11") (pin "7") (pinfunction "Q1_7") (pintype "output"))
    )
    (net (code "179") (name "SR08") (class "Default")
      (node (ref "E06") (pin "7") (pinfunction "Q1_7") (pintype "output"))
      (node (ref "E15") (pin "10") (pinfunction "A2_10") (pintype "input"))
    )
    (net (code "180") (name "SR09") (class "Default")
      (node (ref "E15") (pin "15") (pinfunction "A3_15") (pintype "input"))
      (node (ref "E16") (pin "5") (pinfunction "Q0_5") (pintype "output"))
    )
    (net (code "181") (name "SR10") (class "Default")
      (node (ref "E11") (pin "5") (pinfunction "Q0_5") (pintype "output"))
      (node (ref "E15") (pin "6") (pinfunction "A1_6") (pintype "input"))
    )
    (net (code "182") (name "SR11") (class "Default")
      (node (ref "E06") (pin "5") (pinfunction "Q0_5") (pintype "output"))
      (node (ref "E15") (pin "1") (pinfunction "A0_1") (pintype "input"))
    )
    (net (code "183") (name "SYNC") (class "Default")
      (node (ref "E09") (pin "9") (pinfunction "Q_9") (pintype "output"))
      (node (ref "E27") (pin "11") (pinfunction "I2_11") (pintype "input"))
      (node (ref "E42") (pin "2") (pinfunction "I1_2") (pintype "input"))
      (node (ref "E42") (pin "5") (pinfunction "I0_5") (pintype "input"))
    )
    (net (code "184") (name "S{slash}~{G}") (class "Default")
      (node (ref "E46") (pin "13") (pinfunction "O_13") (pintype "open_collector"))
      (node (ref "J1") (pin "JJ") (pinfunction "30_JJ") (pintype "bidirectional"))
    )
    (net (code "185") (name "TP3") (class "Default")
      (node (ref "E20") (pin "11") (pinfunction "I0_11") (pintype "input"))
      (node (ref "EDGE$") (pin "CH2") (pinfunction "1_CH2") (pintype "bidirectional"))
    )
    (net (code "186") (name "TP4") (class "Default")
      (node (ref "E44") (pin "5") (pinfunction "I1_5") (pintype "input"))
      (node (ref "EDGE$") (pin "CJ2") (pinfunction "1_CJ2") (pintype "bidirectional"))
    )
    (net (code "187") (name "TPG0") (class "Default")
      (node (ref "E14") (pin "9") (pinfunction "Q_9") (pintype "output"))
      (node (ref "E23") (pin "13") (pinfunction "I2_13") (pintype "input"))
    )
    (net (code "188") (name "T{slash}M_ENABLE") (class "Default")
      (node (ref "E46") (pin "4") (pinfunction "O_4") (pintype "open_collector"))
      (node (ref "J1") (pin "NN") (pinfunction "34_NN") (pintype "bidirectional"))
    )
    (net (code "189") (name "UNITH") (class "Default")
      (node (ref "E39") (pin "10") (pinfunction "O_10") (pintype "open_collector"))
      (node (ref "J1") (pin "LL") (pinfunction "32_LL") (pintype "bidirectional"))
    )
    (net (code "190") (name "VCC") (class "Default")
      (node (ref "C1") (pin "1") (pinfunction "1_1") (pintype "passive"))
      (node (ref "C10") (pin "1") (pinfunction "1_1") (pintype "passive"))
      (node (ref "C11") (pin "1") (pinfunction "1_1") (pintype "passive"))
      (node (ref "C12") (pin "1") (pinfunction "1_1") (pintype "passive"))
      (node (ref "C13") (pin "1") (pinfunction "1_1") (pintype "passive"))
      (node (ref "C14") (pin "1") (pinfunction "1_1") (pintype "passive"))
      (node (ref "C15") (pin "1") (pinfunction "1_1") (pintype "passive"))
      (node (ref "C16") (pin "1") (pinfunction "1_1") (pintype "passive"))
      (node (ref "C17") (pin "1") (pinfunction "1_1") (pintype "passive"))
      (node (ref "C18") (pin "1") (pinfunction "1_1") (pintype "passive"))
      (node (ref "C19") (pin "1") (pinfunction "1_1") (pintype "passive"))
      (node (ref "C2") (pin "1") (pinfunction "1_1") (pintype "passive"))
      (node (ref "C20") (pin "1") (pinfunction "1_1") (pintype "passive"))
      (node (ref "C21") (pin "1") (pinfunction "1_1") (pintype "passive"))
      (node (ref "C22") (pin "1") (pinfunction "1_1") (pintype "passive"))
      (node (ref "C23") (pin "1") (pinfunction "1_1") (pintype "passive"))
      (node (ref "C24") (pin "1") (pinfunction "1_1") (pintype "passive"))
      (node (ref "C25") (pin "1") (pinfunction "1_1") (pintype "passive"))
      (node (ref "C26") (pin "1") (pinfunction "1_1") (pintype "passive"))
      (node (ref "C27") (pin "1") (pinfunction "1_1") (pintype "passive"))
      (node (ref "C28") (pin "1") (pinfunction "1_1") (pintype "passive"))
      (node (ref "C29") (pin "1") (pinfunction "1_1") (pintype "passive"))
      (node (ref "C3") (pin "1") (pinfunction "1_1") (pintype "passive"))
      (node (ref "C30") (pin "1") (pinfunction "1_1") (pintype "passive"))
      (node (ref "C31") (pin "1") (pinfunction "1_1") (pintype "passive"))
      (node (ref "C32") (pin "1") (pinfunction "1_1") (pintype "passive"))
      (node (ref "C33") (pin "1") (pinfunction "1_1") (pintype "passive"))
      (node (ref "C34") (pin "+") (pinfunction "+_+") (pintype "passive"))
      (node (ref "C35") (pin "+") (pinfunction "+_+") (pintype "passive"))
      (node (ref "C4") (pin "1") (pinfunction "1_1") (pintype "passive"))
      (node (ref "C43") (pin "1") (pinfunction "1_1") (pintype "passive"))
      (node (ref "C45") (pin "1") (pinfunction "1_1") (pintype "passive"))
      (node (ref "C46") (pin "+") (pinfunction "+_+") (pintype "passive"))
      (node (ref "C5") (pin "1") (pinfunction "1_1") (pintype "passive"))
      (node (ref "C6") (pin "1") (pinfunction "1_1") (pintype "passive"))
      (node (ref "C7") (pin "1") (pinfunction "1_1") (pintype "passive"))
      (node (ref "C8") (pin "1") (pinfunction "1_1") (pintype "passive"))
      (node (ref "C9") (pin "1") (pinfunction "1_1") (pintype "passive"))
      (node (ref "E25") (pin "14") (pinfunction "14_14") (pintype "passive"))
      (node (ref "EDGE$") (pin "AA2") (pinfunction "1_AA2") (pintype "bidirectional"))
      (node (ref "EDGE$") (pin "BA2") (pinfunction "1_BA2") (pintype "bidirectional"))
      (node (ref "EDGE$") (pin "CA2") (pinfunction "1_CA2") (pintype "bidirectional"))
      (node (ref "R1") (pin "2") (pinfunction "2_2") (pintype "passive"))
      (node (ref "R10") (pin "2") (pinfunction "2_2") (pintype "passive"))
      (node (ref "R11") (pin "2") (pinfunction "2_2") (pintype "passive"))
      (node (ref "R12") (pin "2") (pinfunction "2_2") (pintype "passive"))
      (node (ref "R13") (pin "1") (pinfunction "1_1") (pintype "passive"))
      (node (ref "R14") (pin "1") (pinfunction "1_1") (pintype "passive"))
      (node (ref "R15") (pin "2") (pinfunction "2_2") (pintype "passive"))
      (node (ref "R16") (pin "2") (pinfunction "2_2") (pintype "passive"))
      (node (ref "R17") (pin "2") (pinfunction "2_2") (pintype "passive"))
      (node (ref "R18") (pin "2") (pinfunction "2_2") (pintype "passive"))
      (node (ref "R19") (pin "2") (pinfunction "2_2") (pintype "passive"))
      (node (ref "R2") (pin "2") (pinfunction "2_2") (pintype "passive"))
      (node (ref "R20") (pin "2") (pinfunction "2_2") (pintype "passive"))
      (node (ref "R21") (pin "2") (pinfunction "2_2") (pintype "passive"))
      (node (ref "R22") (pin "1") (pinfunction "1_1") (pintype "passive"))
      (node (ref "R23") (pin "2") (pinfunction "2_2") (pintype "passive"))
      (node (ref "R24") (pin "2") (pinfunction "2_2") (pintype "passive"))
      (node (ref "R26") (pin "2") (pinfunction "S_2") (pintype "passive"))
      (node (ref "R26") (pin "3") (pinfunction "E_3") (pintype "passive"))
      (node (ref "R27") (pin "2") (pinfunction "2_2") (pintype "passive"))
      (node (ref "R3") (pin "2") (pinfunction "2_2") (pintype "passive"))
      (node (ref "R4") (pin "2") (pinfunction "2_2") (pintype "passive"))
      (node (ref "R42") (pin "1") (pinfunction "1_1") (pintype "passive"))
      (node (ref "R5") (pin "2") (pinfunction "2_2") (pintype "passive"))
      (node (ref "R6") (pin "2") (pinfunction "2_2") (pintype "passive"))
      (node (ref "R7") (pin "2") (pinfunction "2_2") (pintype "passive"))
      (node (ref "R8") (pin "2") (pinfunction "2_2") (pintype "passive"))
      (node (ref "R9") (pin "2") (pinfunction "2_2") (pintype "passive"))
    )
    (net (code "191") (name "WD_ENAB") (class "Default")
      (node (ref "E46") (pin "10") (pinfunction "O_10") (pintype "open_collector"))
      (node (ref "J1") (pin "Z") (pinfunction "22_Z") (pintype "bidirectional"))
    )
    (net (code "192") (name "WPT") (class "Default")
      (node (ref "E39") (pin "6") (pinfunction "O_6") (pintype "open_collector"))
      (node (ref "J1") (pin "BB") (pinfunction "24_BB") (pintype "bidirectional"))
    )
    (net (code "193") (name "WRT_ECHO") (class "Default")
      (node (ref "C47") (pin "1") (pinfunction "1_1") (pintype "passive"))
      (node (ref "J1") (pin "T") (pinfunction "16_T") (pintype "bidirectional"))
      (node (ref "R48") (pin "1") (pinfunction "1_1") (pintype "passive"))
    )
    (net (code "194") (name "unconnected-(E04A-Q-Pad13)") (class "Default")
      (node (ref "E04") (pin "13") (pinfunction "Q_13") (pintype "output"))
    )
    (net (code "195") (name "unconnected-(E04B-~{Q}-Pad12)") (class "Default")
      (node (ref "E04") (pin "12") (pinfunction "~{Q}_12") (pintype "output"))
    )
    (net (code "196") (name "unconnected-(E06A-Q4-Pad12)") (class "Default")
      (node (ref "E06") (pin "12") (pinfunction "Q4_12") (pintype "output"))
    )
    (net (code "197") (name "unconnected-(E08A-~{Q}-Pad4)") (class "Default")
      (node (ref "E08") (pin "4") (pinfunction "~{Q}_4") (pintype "output"))
    )
    (net (code "198") (name "unconnected-(E09A-~{Q}-Pad6)") (class "Default")
      (node (ref "E09") (pin "6") (pinfunction "~{Q}_6") (pintype "output"))
    )
    (net (code "199") (name "unconnected-(E11A-Q4-Pad12)") (class "Default")
      (node (ref "E11") (pin "12") (pinfunction "Q4_12") (pintype "output"))
    )
    (net (code "200") (name "unconnected-(E13A-D2-Pad3)") (class "Default")
      (node (ref "E13") (pin "3") (pinfunction "D2_3") (pintype "input"))
    )
    (net (code "201") (name "unconnected-(E13A-Q1-Pad16)") (class "Default")
      (node (ref "E13") (pin "16") (pinfunction "Q1_16") (pintype "output"))
    )
    (net (code "202") (name "unconnected-(E13A-Q2-Pad15)") (class "Default")
      (node (ref "E13") (pin "15") (pinfunction "Q2_15") (pintype "output"))
    )
    (net (code "203") (name "unconnected-(E13A-Q3-Pad10)") (class "Default")
      (node (ref "E13") (pin "10") (pinfunction "Q3_10") (pintype "output"))
    )
    (net (code "204") (name "unconnected-(E13A-Q4-Pad9)") (class "Default")
      (node (ref "E13") (pin "9") (pinfunction "Q4_9") (pintype "output"))
    )
    (net (code "205") (name "unconnected-(E13A-~{Q2}-Pad14)") (class "Default")
      (node (ref "E13") (pin "14") (pinfunction "~{Q2}_14") (pintype "output"))
    )
    (net (code "206") (name "unconnected-(E16A-Q4-Pad12)") (class "Default")
      (node (ref "E16") (pin "12") (pinfunction "Q4_12") (pintype "output"))
    )
    (net (code "207") (name "unconnected-(E21A-Q4-Pad12)") (class "Default")
      (node (ref "E21") (pin "12") (pinfunction "Q4_12") (pintype "output"))
    )
    (net (code "208") (name "unconnected-(E25-Pad1)") (class "Default")
      (node (ref "E25") (pin "1") (pinfunction "1_1") (pintype "passive"))
    )
    (net (code "209") (name "unconnected-(E25-Pad2)") (class "Default")
      (node (ref "E25") (pin "2") (pinfunction "2_2") (pintype "passive"))
    )
    (net (code "210") (name "unconnected-(E25-Pad3)") (class "Default")
      (node (ref "E25") (pin "3") (pinfunction "3_3") (pintype "passive"))
    )
    (net (code "211") (name "unconnected-(E25-Pad4)") (class "Default")
      (node (ref "E25") (pin "4") (pinfunction "4_4") (pintype "passive"))
    )
    (net (code "212") (name "unconnected-(E25-Pad5)") (class "Default")
      (node (ref "E25") (pin "5") (pinfunction "5_5") (pintype "passive"))
    )
    (net (code "213") (name "unconnected-(E25-Pad6)") (class "Default")
      (node (ref "E25") (pin "6") (pinfunction "6_6") (pintype "passive"))
    )
    (net (code "214") (name "unconnected-(E25-Pad8)") (class "Default")
      (node (ref "E25") (pin "8") (pinfunction "8_8") (pintype "passive"))
    )
    (net (code "215") (name "unconnected-(E25-Pad9)") (class "Default")
      (node (ref "E25") (pin "9") (pinfunction "9_9") (pintype "passive"))
    )
    (net (code "216") (name "unconnected-(E25-Pad10)") (class "Default")
      (node (ref "E25") (pin "10") (pinfunction "10_10") (pintype "passive"))
    )
    (net (code "217") (name "unconnected-(E25-Pad11)") (class "Default")
      (node (ref "E25") (pin "11") (pinfunction "11_11") (pintype "passive"))
    )
    (net (code "218") (name "unconnected-(E25-Pad12)") (class "Default")
      (node (ref "E25") (pin "12") (pinfunction "12_12") (pintype "passive"))
    )
    (net (code "219") (name "unconnected-(E25-Pad13)") (class "Default")
      (node (ref "E25") (pin "13") (pinfunction "13_13") (pintype "passive"))
    )
    (net (code "220") (name "unconnected-(E29A-Q2-Pad9)") (class "Default")
      (node (ref "E29") (pin "9") (pinfunction "Q2_9") (pintype "output"))
    )
    (net (code "221") (name "unconnected-(E29A-Q3-Pad11)") (class "Default")
      (node (ref "E29") (pin "11") (pinfunction "Q3_11") (pintype "output"))
    )
    (net (code "222") (name "unconnected-(E29A-Q4-Pad12)") (class "Default")
      (node (ref "E29") (pin "12") (pinfunction "Q4_12") (pintype "output"))
    )
    (net (code "223") (name "unconnected-(E36A-QB-Pad9)") (class "Default")
      (node (ref "E36") (pin "9") (pinfunction "QB_9") (pintype "output"))
    )
    (net (code "224") (name "unconnected-(E36A-QC-Pad8)") (class "Default")
      (node (ref "E36") (pin "8") (pinfunction "QC_8") (pintype "output"))
    )
    (net (code "225") (name "unconnected-(E40A-I3-Pad4)") (class "Default")
      (node (ref "E40") (pin "4") (pinfunction "I3_4") (pintype "input"))
    )
    (net (code "226") (name "unconnected-(E40A-I5-Pad6)") (class "Default")
      (node (ref "E40") (pin "6") (pinfunction "I5_6") (pintype "input"))
    )
    (net (code "227") (name "unconnected-(E45A-0-Pad13)") (class "Default")
      (node (ref "E45") (pin "13") (pinfunction "0_13") (pintype "output"))
    )
    (net (code "228") (name "unconnected-(E45A-8-Pad6)") (class "Default")
      (node (ref "E45") (pin "6") (pinfunction "8_6") (pintype "output"))
    )
    (net (code "229") (name "unconnected-(E45A-9-Pad7)") (class "Default")
      (node (ref "E45") (pin "7") (pinfunction "9_7") (pintype "output"))
    )
    (net (code "230") (name "unconnected-(J1-14-PadR)") (class "Default")
      (node (ref "J1") (pin "R") (pinfunction "14_R") (pintype "bidirectional"))
    )
    (net (code "231") (name "~{CC_67X}") (class "Default")
      (node (ref "E07") (pin "11") (pinfunction "I0_11") (pintype "input"))
      (node (ref "E07") (pin "5") (pinfunction "I1_5") (pintype "input"))
      (node (ref "E07") (pin "6") (pinfunction "I0_6") (pintype "input"))
      (node (ref "E07") (pin "9") (pinfunction "I0_9") (pintype "input"))
      (node (ref "E12") (pin "10") (pinfunction "I1_10") (pintype "input"))
      (node (ref "E12") (pin "11") (pinfunction "I0_11") (pintype "input"))
      (node (ref "E12") (pin "4") (pinfunction "I0_4") (pintype "input"))
      (node (ref "E12") (pin "6") (pinfunction "I0_6") (pintype "input"))
      (node (ref "E17") (pin "11") (pinfunction "I0_11") (pintype "input"))
      (node (ref "E17") (pin "4") (pinfunction "I0_4") (pintype "input"))
      (node (ref "E17") (pin "6") (pinfunction "I0_6") (pintype "input"))
      (node (ref "E17") (pin "9") (pinfunction "I0_9") (pintype "input"))
      (node (ref "E26") (pin "10") (pinfunction "O_10") (pintype "output"))
      (node (ref "E44") (pin "10") (pinfunction "I1_10") (pintype "input"))
      (node (ref "E44") (pin "12") (pinfunction "I1_12") (pintype "input"))
      (node (ref "E44") (pin "6") (pinfunction "I0_6") (pintype "input"))
      (node (ref "E45") (pin "2") (pinfunction "D_2") (pintype "input"))
      (node (ref "R6") (pin "1") (pinfunction "1_1") (pintype "passive"))
    )
    (net (code "232") (name "~{CC_CLK_TE}") (class "Default")
      (node (ref "E26") (pin "6") (pinfunction "O_6") (pintype "output"))
      (node (ref "E27") (pin "2") (pinfunction "I1_2") (pintype "input"))
    )
    (net (code "233") (name "~{CC_DTP0}") (class "Default")
      (node (ref "E22") (pin "2") (pinfunction "I1_2") (pintype "input"))
      (node (ref "E31") (pin "13") (pinfunction "I_13") (pintype "input"))
      (node (ref "E31") (pin "4") (pinfunction "O_4") (pintype "output"))
      (node (ref "E38") (pin "13") (pinfunction "I1_13") (pintype "input"))
    )
    (net (code "234") (name "~{CC_DTP1}") (class "Default")
      (node (ref "E22") (pin "12") (pinfunction "I0_12") (pintype "input"))
      (node (ref "E22") (pin "5") (pinfunction "I1_5") (pintype "input"))
      (node (ref "E22") (pin "9") (pinfunction "I0_9") (pintype "input"))
      (node (ref "E31") (pin "2") (pinfunction "O_2") (pintype "output"))
    )
    (net (code "235") (name "~{CC_INIT}") (class "Default")
      (node (ref "E27") (pin "1") (pinfunction "I0_1") (pintype "input"))
      (node (ref "E32") (pin "10") (pinfunction "O_10") (pintype "output"))
      (node (ref "E34") (pin "1") (pinfunction "CLR_1") (pintype "input"))
      (node (ref "E34") (pin "13") (pinfunction "CLR_13") (pintype "input"))
      (node (ref "E40") (pin "12") (pinfunction "I7_12") (pintype "input"))
    )
    (net (code "236") (name "~{CC_RUN}") (class "Default")
      (node (ref "E20") (pin "14") (pinfunction "O_14") (pintype "output"))
      (node (ref "E26") (pin "13") (pinfunction "I_13") (pintype "input"))
      (node (ref "E40") (pin "3") (pinfunction "I2_3") (pintype "input"))
    )
    (net (code "237") (name "~{CC_SDLC}") (class "Default")
      (node (ref "E19") (pin "13") (pinfunction "I1_13") (pintype "input"))
      (node (ref "E37") (pin "12") (pinfunction "I1_12") (pintype "input"))
      (node (ref "E45") (pin "9") (pinfunction "4_9") (pintype "output"))
    )
    (net (code "238") (name "~{CC_SDLD}") (class "Default")
      (node (ref "E02") (pin "3") (pinfunction "I1_3") (pintype "input"))
      (node (ref "E06") (pin "13") (pinfunction "S_13") (pintype "input"))
      (node (ref "E11") (pin "13") (pinfunction "S_13") (pintype "input"))
      (node (ref "E16") (pin "13") (pinfunction "S_13") (pintype "input"))
      (node (ref "E27") (pin "5") (pinfunction "I2_5") (pintype "input"))
      (node (ref "E33") (pin "12") (pinfunction "I1_12") (pintype "input"))
      (node (ref "E45") (pin "3") (pinfunction "5_3") (pintype "output"))
    )
    (net (code "239") (name "~{CC_SDRC}") (class "Default")
      (node (ref "E05") (pin "9") (pinfunction "S0_9") (pintype "input"))
      (node (ref "E10") (pin "9") (pinfunction "S0_9") (pintype "input"))
      (node (ref "E15") (pin "9") (pinfunction "S0_9") (pintype "input"))
      (node (ref "E27") (pin "3") (pinfunction "I0_3") (pintype "input"))
      (node (ref "E45") (pin "4") (pinfunction "6_4") (pintype "output"))
    )
    (net (code "240") (name "~{CC_SDRD}") (class "Default")
      (node (ref "E05") (pin "7") (pinfunction "S1_7") (pintype "input"))
      (node (ref "E10") (pin "7") (pinfunction "S1_7") (pintype "input"))
      (node (ref "E15") (pin "7") (pinfunction "S1_7") (pintype "input"))
      (node (ref "E27") (pin "4") (pinfunction "I1_4") (pintype "input"))
      (node (ref "E45") (pin "5") (pinfunction "7_5") (pintype "output"))
    )
    (net (code "241") (name "~{CC_SDSQ}") (class "Default")
      (node (ref "E32") (pin "1") (pinfunction "I_1") (pintype "input"))
      (node (ref "E45") (pin "10") (pinfunction "3_10") (pintype "output"))
    )
    (net (code "242") (name "~{CC_SDSS}") (class "Default")
      (node (ref "E32") (pin "3") (pinfunction "I_3") (pintype "input"))
      (node (ref "E45") (pin "12") (pinfunction "1_12") (pintype "output"))
    )
    (net (code "243") (name "~{CC_SDST}") (class "Default")
      (node (ref "E32") (pin "5") (pinfunction "I_5") (pintype "input"))
      (node (ref "E45") (pin "11") (pinfunction "2_11") (pintype "output"))
    )
    (net (code "244") (name "~{CC_SETDLY}") (class "Default")
      (node (ref "E03") (pin "5") (pinfunction "Q_5") (pintype "output"))
      (node (ref "E22") (pin "4") (pinfunction "I0_4") (pintype "input"))
    )
    (net (code "245") (name "~{CC_TP3}") (class "Default")
      (node (ref "E01") (pin "1") (pinfunction "I_1") (pintype "input"))
      (node (ref "E02") (pin "2") (pinfunction "I0_2") (pintype "input"))
      (node (ref "E20") (pin "13") (pinfunction "O_13") (pintype "output"))
      (node (ref "E37") (pin "11") (pinfunction "I0_11") (pintype "input"))
    )
    (net (code "246") (name "~{CC_TPG1}") (class "Default")
      (node (ref "E14") (pin "6") (pinfunction "~{Q}_6") (pintype "output"))
      (node (ref "E42") (pin "1") (pinfunction "I0_1") (pintype "input"))
    )
    (net (code "247") (name "~{CC_TPG_CLK}") (class "Default")
      (node (ref "C40") (pin "1") (pinfunction "1_1") (pintype "passive"))
      (node (ref "E04") (pin "10") (pinfunction "B_10") (pintype "input"))
      (node (ref "R25") (pin "1") (pinfunction "1_1") (pintype "passive"))
    )
    (net (code "248") (name "~{CC_UNIT}") (class "Default")
      (node (ref "E05") (pin "11") (pinfunction "B2_11") (pintype "input"))
      (node (ref "E34") (pin "8") (pinfunction "~{Q}_8") (pintype "output"))
    )
    (net (code "249") (name "~{CC_UTS}") (class "Default")
      (node (ref "E02") (pin "11") (pinfunction "I0_11") (pintype "input"))
      (node (ref "E03") (pin "8") (pinfunction "~{Q}_8") (pintype "output"))
    )
    (net (code "250") (name "~{DF_HLD}") (class "Default")
      (node (ref "E10") (pin "11") (pinfunction "B2_11") (pintype "input"))
      (node (ref "E32") (pin "8") (pinfunction "O_8") (pintype "output"))
      (node (ref "E40") (pin "2") (pinfunction "I1_2") (pintype "input"))
    )
    (net (code "251") (name "~{DF_SEL_ER}") (class "Default")
      (node (ref "E32") (pin "13") (pinfunction "I_13") (pintype "input"))
      (node (ref "E40") (pin "5") (pinfunction "I4_5") (pintype "input"))
      (node (ref "Q2") (pin "3") (pinfunction "C_3") (pintype "passive"))
      (node (ref "Q3") (pin "3") (pinfunction "C_3") (pintype "passive"))
      (node (ref "R11") (pin "1") (pinfunction "1_1") (pintype "passive"))
    )
    (net (code "252") (name "~{DF_TIME_ER}") (class "Default")
      (node (ref "E27") (pin "12") (pinfunction "O_12") (pintype "output"))
      (node (ref "E35") (pin "5") (pinfunction "I2_5") (pintype "input"))
      (node (ref "E40") (pin "1") (pinfunction "I0_1") (pintype "input"))
    )
    (net (code "253") (name "~{MTR0}") (class "Default")
      (node (ref "E10") (pin "5") (pinfunction "B1_5") (pintype "input"))
      (node (ref "E29") (pin "7") (pinfunction "Q1_7") (pintype "output"))
    )
    (net (code "254") (name "~{MTR1}") (class "Default")
      (node (ref "E10") (pin "2") (pinfunction "B0_2") (pintype "input"))
      (node (ref "E29") (pin "5") (pinfunction "Q0_5") (pintype "output"))
    )
    (net (code "255") (name "~{MTR2}") (class "Default")
      (node (ref "E15") (pin "11") (pinfunction "B2_11") (pintype "input"))
      (node (ref "E21") (pin "11") (pinfunction "Q3_11") (pintype "output"))
      (node (ref "E29") (pin "4") (pinfunction "D_4") (pintype "input"))
    )
    (net (code "256") (name "~{MTR3}") (class "Default")
      (node (ref "E15") (pin "14") (pinfunction "B3_14") (pintype "input"))
      (node (ref "E21") (pin "9") (pinfunction "Q2_9") (pintype "output"))
    )
    (net (code "257") (name "~{MTR4}") (class "Default")
      (node (ref "E15") (pin "5") (pinfunction "B1_5") (pintype "input"))
      (node (ref "E21") (pin "7") (pinfunction "Q1_7") (pintype "output"))
    )
    (net (code "258") (name "~{MTR5}") (class "Default")
      (node (ref "E15") (pin "2") (pinfunction "B0_2") (pintype "input"))
      (node (ref "E21") (pin "5") (pinfunction "Q0_5") (pintype "output"))
    )
    (net (code "259") (name "~{POWER_OK}") (class "Default")
      (node (ref "E28") (pin "6") (pinfunction "I0_6") (pintype "input"))
      (node (ref "EDGE$") (pin "BV2") (pinfunction "1_BV2") (pintype "bidirectional"))
    )
    (net (code "260") (name "~{RTT}") (class "Default")
      (node (ref "E42") (pin "6") (pinfunction "I1_6") (pintype "input"))
      (node (ref "J1") (pin "J") (pinfunction "8_J") (pintype "bidirectional"))
      (node (ref "R18") (pin "1") (pinfunction "1_1") (pintype "passive"))
    )
    (net (code "261") (name "~{SKIP}") (class "Default")
      (node (ref "E41") (pin "1") (pinfunction "O_1") (pintype "open_collector"))
      (node (ref "E41") (pin "10") (pinfunction "O_10") (pintype "open_collector"))
      (node (ref "E41") (pin "13") (pinfunction "O_13") (pintype "open_collector"))
      (node (ref "EDGE$") (pin "CS1") (pinfunction "1_CS1") (pintype "bidirectional"))
    )
  )
)
